# SI5324_CDR_WR_oscillators.net
KiCad netlist of a schematic drawn in Altium Designer
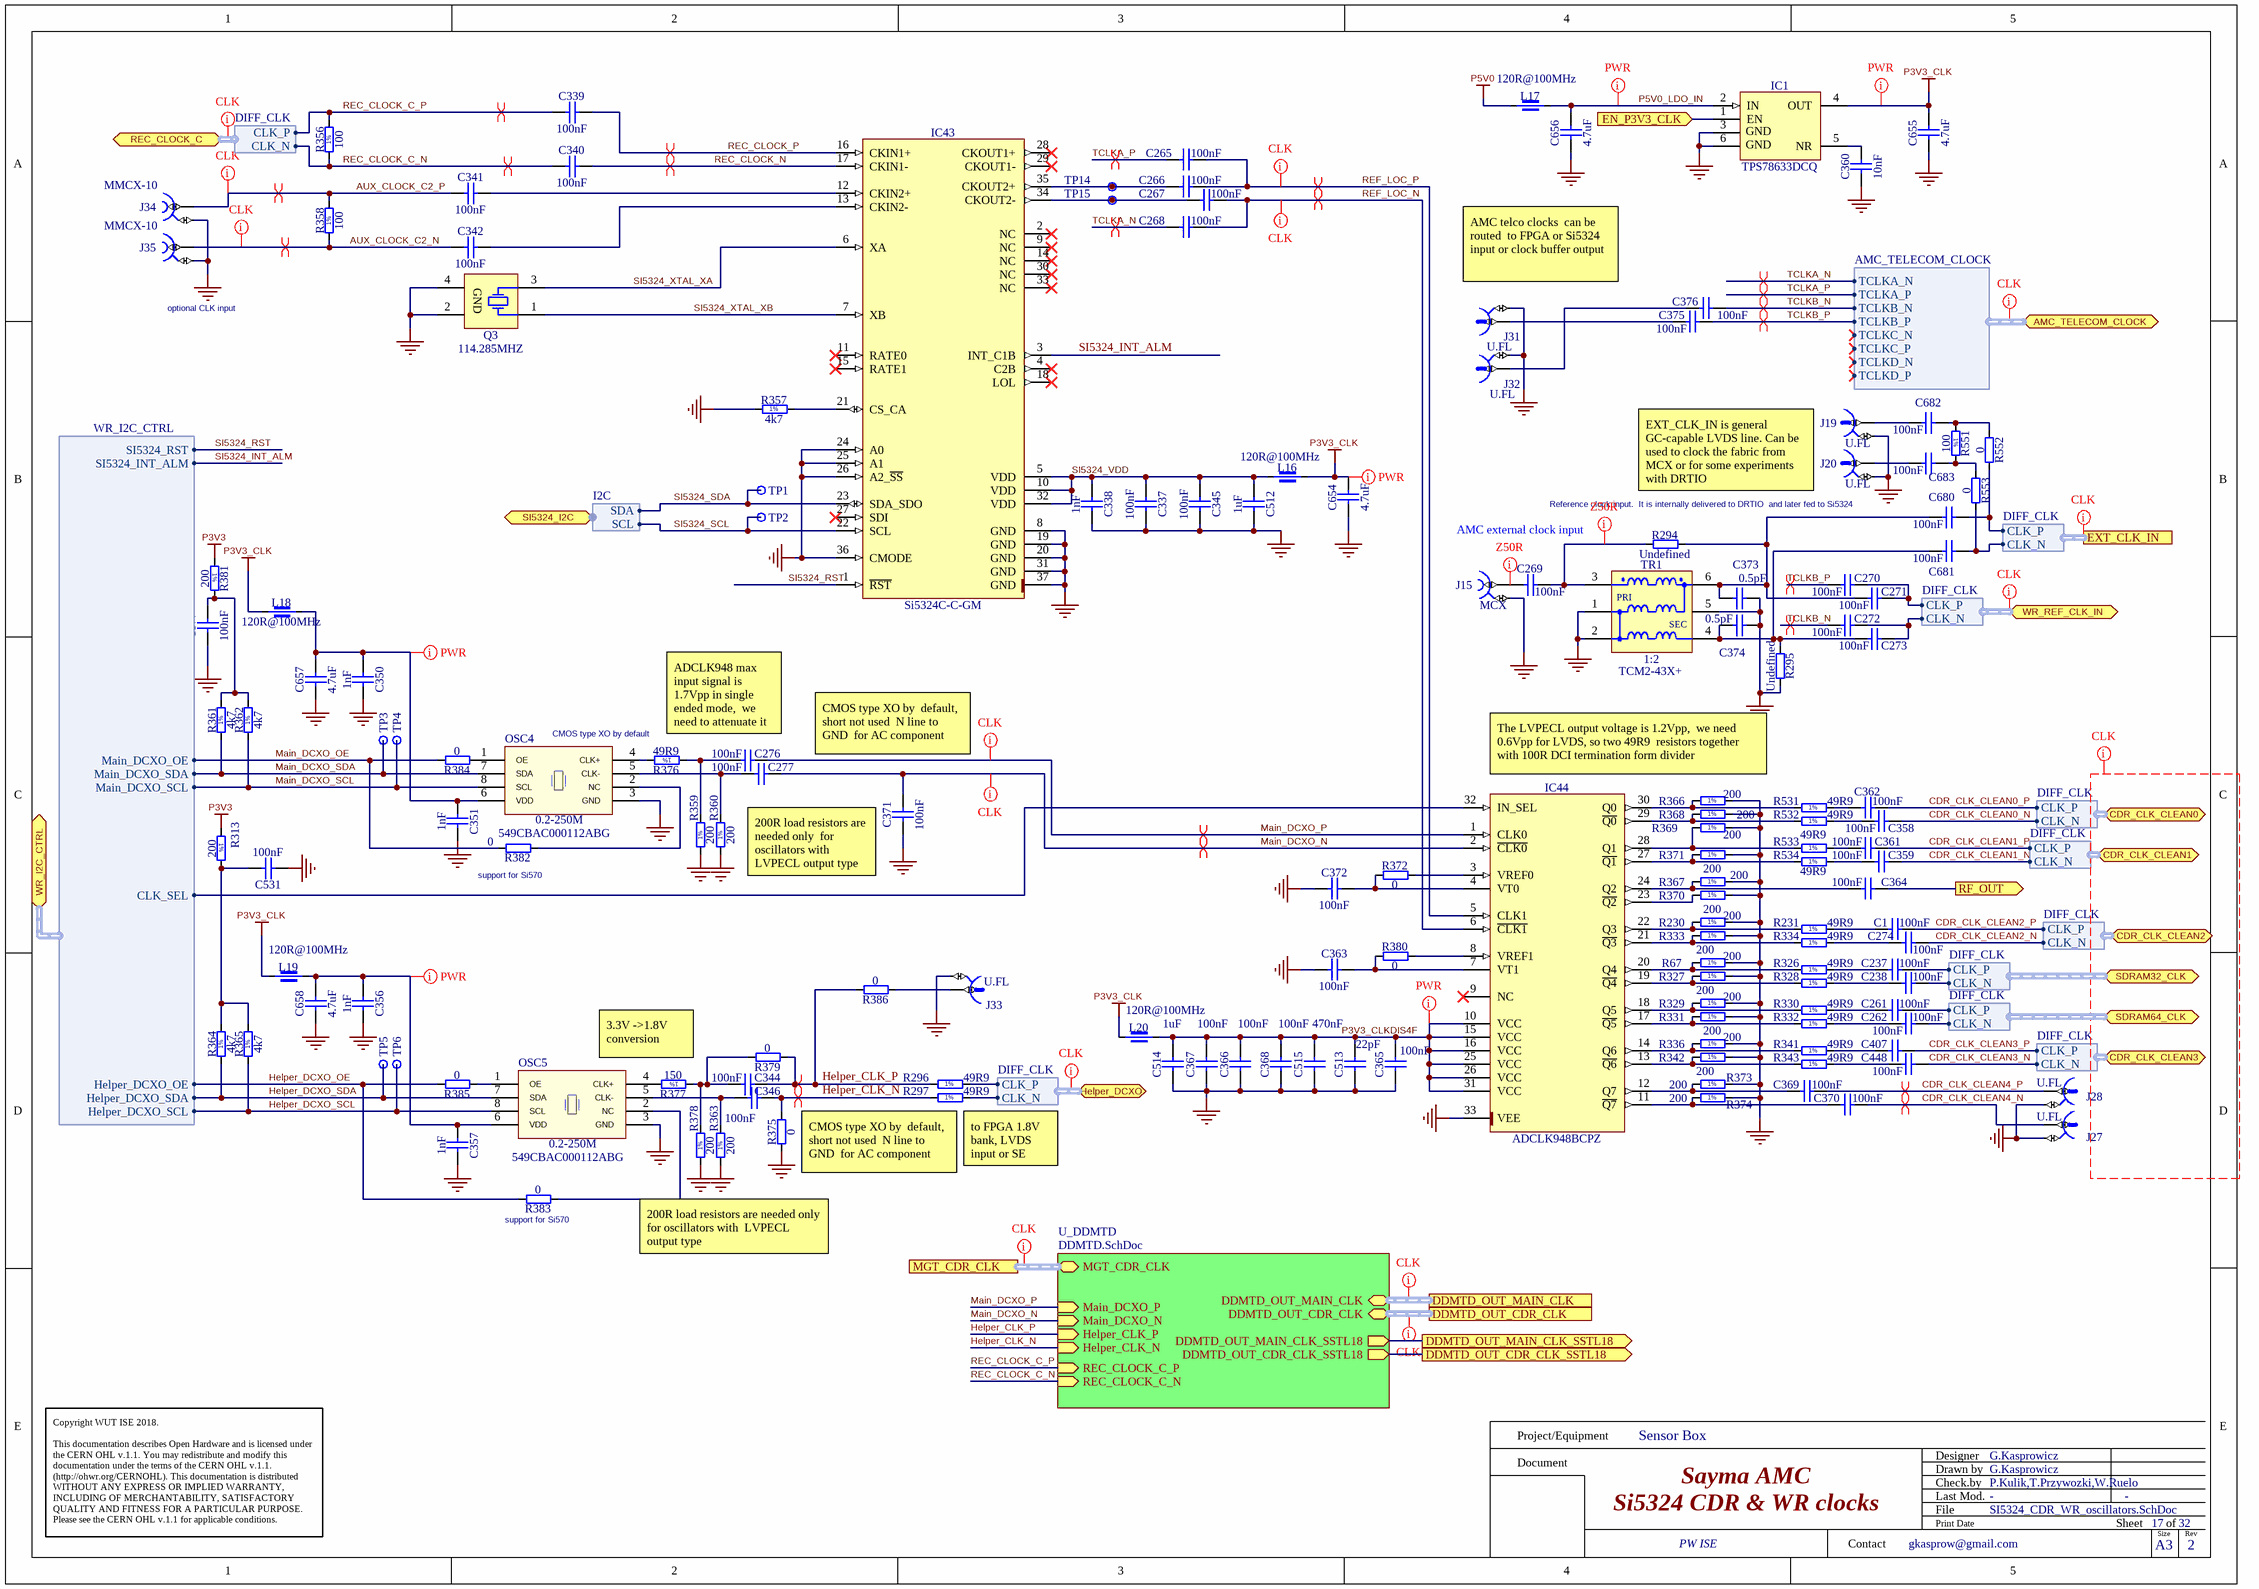
[diagram p0: SI5324_CDR_WR_oscillators.SchDoc]

(export (version "E")
  (design (tool "Eeschema 10.0.6"))
  (components
    (comp (ref "C1")
      (value "100nF")
      (footprint "CAPC0603X33N")
      (description "Non-polarised capacitor")
      (fields
        (field (name "MANUFACTURER PART NUMBER") "CC0201_100NF_6.3V_10%_X5R")
        (field (name "MANUFACTURER") "GENERIC")
        (field (name "AUTHOR") "CERN DEM JLC")
      )
      (libsource (lib "Capacitors") (part "Capacitor - non polarized"))
    )
    (comp (ref "C237")
      (value "100nF")
      (footprint "CAPC0603X33N")
      (description "Non-polarised capacitor")
      (fields
        (field (name "MANUFACTURER PART NUMBER") "CC0201_100NF_6.3V_10%_X5R")
        (field (name "MANUFACTURER") "GENERIC")
        (field (name "AUTHOR") "CERN DEM JLC")
      )
      (libsource (lib "Capacitors") (part "Capacitor - non polarized"))
    )
    (comp (ref "C238")
      (value "100nF")
      (footprint "CAPC0603X33N")
      (description "Non-polarised capacitor")
      (fields
        (field (name "MANUFACTURER PART NUMBER") "CC0201_100NF_6.3V_10%_X5R")
        (field (name "MANUFACTURER") "GENERIC")
        (field (name "AUTHOR") "CERN DEM JLC")
      )
      (libsource (lib "Capacitors") (part "Capacitor - non polarized"))
    )
    (comp (ref "C261")
      (value "100nF")
      (footprint "CAPC0603X33N")
      (description "Non-polarised capacitor")
      (fields
        (field (name "MANUFACTURER PART NUMBER") "CC0201_100NF_6.3V_10%_X5R")
        (field (name "MANUFACTURER") "GENERIC")
        (field (name "AUTHOR") "CERN DEM JLC")
      )
      (libsource (lib "Capacitors") (part "Capacitor - non polarized"))
    )
    (comp (ref "C262")
      (value "100nF")
      (footprint "CAPC0603X33N")
      (description "Non-polarised capacitor")
      (fields
        (field (name "MANUFACTURER PART NUMBER") "CC0201_100NF_6.3V_10%_X5R")
        (field (name "MANUFACTURER") "GENERIC")
        (field (name "AUTHOR") "CERN DEM JLC")
      )
      (libsource (lib "Capacitors") (part "Capacitor - non polarized"))
    )
    (comp (ref "C265")
      (value "100nF")
      (footprint "CAPC1005X55N")
      (description "Non-polarised capacitor")
      (fields
        (field (name "MANUFACTURER PART NUMBER") "CC0402_100NF_16V_10%_X5R")
        (field (name "MANUFACTURER") "GENERIC")
        (field (name "AUTHOR") "CERN DEM JLC")
      )
      (libsource (lib "Capacitors") (part "Capacitor - non polarized"))
    )
    (comp (ref "C266")
      (value "100nF")
      (footprint "CAPC1005X55N")
      (description "Non-polarised capacitor")
      (fields
        (field (name "MANUFACTURER PART NUMBER") "CC0402_100NF_16V_10%_X5R")
        (field (name "MANUFACTURER") "GENERIC")
        (field (name "AUTHOR") "CERN DEM JLC")
      )
      (libsource (lib "Capacitors") (part "Capacitor - non polarized"))
    )
    (comp (ref "C267")
      (value "100nF")
      (footprint "CAPC1005X55N")
      (description "Non-polarised capacitor")
      (fields
        (field (name "MANUFACTURER PART NUMBER") "CC0402_100NF_16V_10%_X5R")
        (field (name "MANUFACTURER") "GENERIC")
        (field (name "AUTHOR") "CERN DEM JLC")
      )
      (libsource (lib "Capacitors") (part "Capacitor - non polarized"))
    )
    (comp (ref "C268")
      (value "100nF")
      (footprint "CAPC1005X55N")
      (description "Non-polarised capacitor")
      (fields
        (field (name "MANUFACTURER PART NUMBER") "CC0402_100NF_16V_10%_X5R")
        (field (name "MANUFACTURER") "GENERIC")
        (field (name "AUTHOR") "CERN DEM JLC")
      )
      (libsource (lib "Capacitors") (part "Capacitor - non polarized"))
    )
    (comp (ref "C269")
      (value "100nF")
      (footprint "CAPC1005X55N")
      (description "Non-polarised capacitor")
      (fields
        (field (name "MANUFACTURER PART NUMBER") "CC0402_100NF_16V_10%_X5R")
        (field (name "MANUFACTURER") "GENERIC")
        (field (name "AUTHOR") "CERN DEM JLC")
      )
      (libsource (lib "Capacitors") (part "Capacitor - non polarized"))
    )
    (comp (ref "C270")
      (value "100nF")
      (footprint "CAPC1005X55N")
      (description "Non-polarised capacitor")
      (fields
        (field (name "MANUFACTURER PART NUMBER") "CC0402_100NF_16V_10%_X5R")
        (field (name "MANUFACTURER") "GENERIC")
        (field (name "AUTHOR") "CERN DEM JLC")
      )
      (libsource (lib "Capacitors") (part "Capacitor - non polarized"))
    )
    (comp (ref "C271")
      (value "100nF")
      (footprint "CAPC1005X55N")
      (description "Non-polarised capacitor")
      (fields
        (field (name "MANUFACTURER PART NUMBER") "CC0402_100NF_16V_10%_X5R")
        (field (name "MANUFACTURER") "GENERIC")
        (field (name "AUTHOR") "CERN DEM JLC")
      )
      (libsource (lib "Capacitors") (part "Capacitor - non polarized"))
    )
    (comp (ref "C272")
      (value "100nF")
      (footprint "CAPC1005X55N")
      (description "Non-polarised capacitor")
      (fields
        (field (name "MANUFACTURER PART NUMBER") "CC0402_100NF_16V_10%_X5R")
        (field (name "MANUFACTURER") "GENERIC")
        (field (name "AUTHOR") "CERN DEM JLC")
      )
      (libsource (lib "Capacitors") (part "Capacitor - non polarized"))
    )
    (comp (ref "C273")
      (value "100nF")
      (footprint "CAPC1005X55N")
      (description "Non-polarised capacitor")
      (fields
        (field (name "MANUFACTURER PART NUMBER") "CC0402_100NF_16V_10%_X5R")
        (field (name "MANUFACTURER") "GENERIC")
        (field (name "AUTHOR") "CERN DEM JLC")
      )
      (libsource (lib "Capacitors") (part "Capacitor - non polarized"))
    )
    (comp (ref "C274")
      (value "100nF")
      (footprint "CAPC0603X33N")
      (description "Non-polarised capacitor")
      (fields
        (field (name "MANUFACTURER PART NUMBER") "CC0201_100NF_6.3V_10%_X5R")
        (field (name "MANUFACTURER") "GENERIC")
        (field (name "AUTHOR") "CERN DEM JLC")
      )
      (libsource (lib "Capacitors") (part "Capacitor - non polarized"))
    )
    (comp (ref "C276")
      (value "100nF")
      (footprint "CAPC1005X55N")
      (description "Non-polarised capacitor")
      (fields
        (field (name "MANUFACTURER PART NUMBER") "CC0402_100NF_16V_10%_X5R")
        (field (name "MANUFACTURER") "GENERIC")
        (field (name "AUTHOR") "CERN DEM JLC")
      )
      (libsource (lib "Capacitors") (part "Capacitor - non polarized"))
    )
    (comp (ref "C277")
      (value "100nF")
      (footprint "CAPC1005X55N")
      (description "Non-polarised capacitor")
      (fields
        (field (name "MANUFACTURER PART NUMBER") "CC0402_100NF_16V_10%_X5R")
        (field (name "MANUFACTURER") "GENERIC")
        (field (name "AUTHOR") "CERN DEM JLC")
      )
      (libsource (lib "Capacitors") (part "Capacitor - non polarized"))
    )
    (comp (ref "C337")
      (value "100nF")
      (footprint "CAPC0603X33N")
      (description "Non-polarised capacitor")
      (fields
        (field (name "MANUFACTURER PART NUMBER") "CC0201_100NF_6.3V_10%_X5R")
        (field (name "MANUFACTURER") "GENERIC")
        (field (name "AUTHOR") "CERN DEM JLC")
      )
      (libsource (lib "Capacitors") (part "Capacitor - non polarized"))
    )
    (comp (ref "C338")
      (value "1nF")
      (footprint "CAPC0603X33N")
      (description "Non-polarised capacitor")
      (fields
        (field (name "MANUFACTURER PART NUMBER") "CC0201_1NF_16V_10%_X5R")
        (field (name "MANUFACTURER") "GENERIC")
        (field (name "AUTHOR") "CERN DEM JLC")
      )
      (libsource (lib "Capacitors") (part "Capacitor - non polarized"))
    )
    (comp (ref "C339")
      (value "100nF")
      (footprint "CAPC0603X33N")
      (description "Non-polarised capacitor")
      (fields
        (field (name "MANUFACTURER PART NUMBER") "CC0201_100NF_6.3V_10%_X5R")
        (field (name "MANUFACTURER") "GENERIC")
        (field (name "AUTHOR") "CERN DEM JLC")
      )
      (libsource (lib "Capacitors") (part "Capacitor - non polarized"))
    )
    (comp (ref "C340")
      (value "100nF")
      (footprint "CAPC0603X33N")
      (description "Non-polarised capacitor")
      (fields
        (field (name "MANUFACTURER PART NUMBER") "CC0201_100NF_6.3V_10%_X5R")
        (field (name "MANUFACTURER") "GENERIC")
        (field (name "AUTHOR") "CERN DEM JLC")
      )
      (libsource (lib "Capacitors") (part "Capacitor - non polarized"))
    )
    (comp (ref "C341")
      (value "100nF")
      (footprint "CAPC0603X33N")
      (description "Non-polarised capacitor")
      (fields
        (field (name "MANUFACTURER PART NUMBER") "CC0201_100NF_6.3V_10%_X5R")
        (field (name "MANUFACTURER") "GENERIC")
        (field (name "AUTHOR") "CERN DEM JLC")
      )
      (libsource (lib "Capacitors") (part "Capacitor - non polarized"))
    )
    (comp (ref "C342")
      (value "100nF")
      (footprint "CAPC0603X33N")
      (description "Non-polarised capacitor")
      (fields
        (field (name "MANUFACTURER PART NUMBER") "CC0201_100NF_6.3V_10%_X5R")
        (field (name "MANUFACTURER") "GENERIC")
        (field (name "AUTHOR") "CERN DEM JLC")
      )
      (libsource (lib "Capacitors") (part "Capacitor - non polarized"))
    )
    (comp (ref "C344")
      (value "100nF")
      (footprint "CAPC1005X55N")
      (description "Non-polarised capacitor")
      (fields
        (field (name "MANUFACTURER PART NUMBER") "CC0402_100NF_16V_10%_X5R")
        (field (name "MANUFACTURER") "GENERIC")
        (field (name "AUTHOR") "CERN DEM JLC")
      )
      (libsource (lib "Capacitors") (part "Capacitor - non polarized"))
    )
    (comp (ref "C345")
      (value "100nF")
      (footprint "CAPC0603X33N")
      (description "Non-polarised capacitor")
      (fields
        (field (name "MANUFACTURER PART NUMBER") "CC0201_100NF_6.3V_10%_X5R")
        (field (name "MANUFACTURER") "GENERIC")
        (field (name "AUTHOR") "CERN DEM JLC")
      )
      (libsource (lib "Capacitors") (part "Capacitor - non polarized"))
    )
    (comp (ref "C346")
      (value "100nF")
      (footprint "CAPC1005X55N")
      (description "Non-polarised capacitor")
      (fields
        (field (name "MANUFACTURER PART NUMBER") "CC0402_100NF_16V_10%_X5R")
        (field (name "MANUFACTURER") "GENERIC")
        (field (name "AUTHOR") "CERN DEM JLC")
      )
      (libsource (lib "Capacitors") (part "Capacitor - non polarized"))
    )
    (comp (ref "C350")
      (value "1nF")
      (footprint "CAPC0603X33N")
      (description "Non-polarised capacitor")
      (fields
        (field (name "MANUFACTURER PART NUMBER") "CC0201_1NF_16V_10%_X5R")
        (field (name "MANUFACTURER") "GENERIC")
        (field (name "AUTHOR") "CERN DEM JLC")
      )
      (libsource (lib "Capacitors") (part "Capacitor - non polarized"))
    )
    (comp (ref "C351")
      (value "1nF")
      (footprint "CAPC0603X33N")
      (description "Non-polarised capacitor")
      (fields
        (field (name "MANUFACTURER PART NUMBER") "CC0201_1NF_16V_10%_X5R")
        (field (name "MANUFACTURER") "GENERIC")
        (field (name "AUTHOR") "CERN DEM JLC")
      )
      (libsource (lib "Capacitors") (part "Capacitor - non polarized"))
    )
    (comp (ref "C356")
      (value "1nF")
      (footprint "CAPC0603X33N")
      (description "Non-polarised capacitor")
      (fields
        (field (name "MANUFACTURER PART NUMBER") "CC0201_1NF_16V_10%_X5R")
        (field (name "MANUFACTURER") "GENERIC")
        (field (name "AUTHOR") "CERN DEM JLC")
      )
      (libsource (lib "Capacitors") (part "Capacitor - non polarized"))
    )
    (comp (ref "C357")
      (value "1nF")
      (footprint "CAPC0603X33N")
      (description "Non-polarised capacitor")
      (fields
        (field (name "MANUFACTURER PART NUMBER") "CC0201_1NF_16V_10%_X5R")
        (field (name "MANUFACTURER") "GENERIC")
        (field (name "AUTHOR") "CERN DEM JLC")
      )
      (libsource (lib "Capacitors") (part "Capacitor - non polarized"))
    )
    (comp (ref "C358")
      (value "100nF")
      (footprint "CAPC0603X33N")
      (description "Non-polarised capacitor")
      (fields
        (field (name "MANUFACTURER PART NUMBER") "CC0201_100NF_6.3V_10%_X5R")
        (field (name "MANUFACTURER") "GENERIC")
        (field (name "AUTHOR") "CERN DEM JLC")
      )
      (libsource (lib "Capacitors") (part "Capacitor - non polarized"))
    )
    (comp (ref "C359")
      (value "100nF")
      (footprint "CAPC0603X33N")
      (description "Non-polarised capacitor")
      (fields
        (field (name "MANUFACTURER PART NUMBER") "CC0201_100NF_6.3V_10%_X5R")
        (field (name "MANUFACTURER") "GENERIC")
        (field (name "AUTHOR") "CERN DEM JLC")
      )
      (libsource (lib "Capacitors") (part "Capacitor - non polarized"))
    )
    (comp (ref "C360")
      (value "10nF")
      (footprint "CAPC1608X87N")
      (description "Non-polarised capacitor")
      (fields
        (field (name "PART NUMBER") "CC0603_10NF_50V_5%_C0G")
        (field (name "VOLTAGE") "50V")
        (field (name "AUTHOR") "CERN DEM JLC")
      )
      (libsource (lib "Capacitors") (part "Capacitor - non polarized"))
    )
    (comp (ref "C361")
      (value "100nF")
      (footprint "CAPC0603X33N")
      (description "Non-polarised capacitor")
      (fields
        (field (name "MANUFACTURER PART NUMBER") "CC0201_100NF_6.3V_10%_X5R")
        (field (name "MANUFACTURER") "GENERIC")
        (field (name "AUTHOR") "CERN DEM JLC")
      )
      (libsource (lib "Capacitors") (part "Capacitor - non polarized"))
    )
    (comp (ref "C362")
      (value "100nF")
      (footprint "CAPC0603X33N")
      (description "Non-polarised capacitor")
      (fields
        (field (name "MANUFACTURER PART NUMBER") "CC0201_100NF_6.3V_10%_X5R")
        (field (name "MANUFACTURER") "GENERIC")
        (field (name "AUTHOR") "CERN DEM JLC")
      )
      (libsource (lib "Capacitors") (part "Capacitor - non polarized"))
    )
    (comp (ref "C363")
      (value "100nF")
      (footprint "CAPC0603X33N")
      (description "Non-polarised capacitor")
      (fields
        (field (name "MANUFACTURER PART NUMBER") "CC0201_100NF_6.3V_10%_X5R")
        (field (name "MANUFACTURER") "GENERIC")
        (field (name "AUTHOR") "CERN DEM JLC")
      )
      (libsource (lib "Capacitors") (part "Capacitor - non polarized"))
    )
    (comp (ref "C364")
      (value "100nF")
      (footprint "CAPC0603X33N")
      (description "Non-polarised capacitor")
      (fields
        (field (name "MANUFACTURER PART NUMBER") "CC0201_100NF_6.3V_10%_X5R")
        (field (name "MANUFACTURER") "GENERIC")
        (field (name "AUTHOR") "CERN DEM JLC")
      )
      (libsource (lib "Capacitors") (part "Capacitor - non polarized"))
    )
    (comp (ref "C365")
      (value "100nF")
      (footprint "CAPC0603X33N")
      (description "Non-polarised capacitor")
      (fields
        (field (name "MANUFACTURER PART NUMBER") "CC0201_100NF_6.3V_10%_X5R")
        (field (name "MANUFACTURER") "GENERIC")
        (field (name "AUTHOR") "CERN DEM JLC")
      )
      (libsource (lib "Capacitors") (part "Capacitor - non polarized"))
    )
    (comp (ref "C366")
      (value "100nF")
      (footprint "CAPC0603X33N")
      (description "Non-polarised capacitor")
      (fields
        (field (name "MANUFACTURER PART NUMBER") "CC0201_100NF_6.3V_10%_X5R")
        (field (name "MANUFACTURER") "GENERIC")
        (field (name "AUTHOR") "CERN DEM JLC")
      )
      (libsource (lib "Capacitors") (part "Capacitor - non polarized"))
    )
    (comp (ref "C367")
      (value "100nF")
      (footprint "CAPC0603X33N")
      (description "Non-polarised capacitor")
      (fields
        (field (name "MANUFACTURER PART NUMBER") "CC0201_100NF_6.3V_10%_X5R")
        (field (name "MANUFACTURER") "GENERIC")
        (field (name "AUTHOR") "CERN DEM JLC")
      )
      (libsource (lib "Capacitors") (part "Capacitor - non polarized"))
    )
    (comp (ref "C368")
      (value "100nF")
      (footprint "CAPC0603X33N")
      (description "Non-polarised capacitor")
      (fields
        (field (name "MANUFACTURER PART NUMBER") "CC0201_100NF_6.3V_10%_X5R")
        (field (name "MANUFACTURER") "GENERIC")
        (field (name "AUTHOR") "CERN DEM JLC")
      )
      (libsource (lib "Capacitors") (part "Capacitor - non polarized"))
    )
    (comp (ref "C369")
      (value "100nF")
      (footprint "CAPC0603X33N")
      (description "Non-polarised capacitor")
      (fields
        (field (name "MANUFACTURER PART NUMBER") "CC0201_100NF_6.3V_10%_X5R")
        (field (name "MANUFACTURER") "GENERIC")
        (field (name "AUTHOR") "CERN DEM JLC")
      )
      (libsource (lib "Capacitors") (part "Capacitor - non polarized"))
    )
    (comp (ref "C370")
      (value "100nF")
      (footprint "CAPC0603X33N")
      (description "Non-polarised capacitor")
      (fields
        (field (name "MANUFACTURER PART NUMBER") "CC0201_100NF_6.3V_10%_X5R")
        (field (name "MANUFACTURER") "GENERIC")
        (field (name "AUTHOR") "CERN DEM JLC")
      )
      (libsource (lib "Capacitors") (part "Capacitor - non polarized"))
    )
    (comp (ref "C371")
      (value "100nF")
      (footprint "CAPC0603X33N")
      (description "Non-polarised capacitor")
      (fields
        (field (name "MANUFACTURER PART NUMBER") "CC0201_100NF_6.3V_10%_X5R")
        (field (name "MANUFACTURER") "GENERIC")
        (field (name "AUTHOR") "CERN DEM JLC")
      )
      (libsource (lib "Capacitors") (part "Capacitor - non polarized"))
    )
    (comp (ref "C372")
      (value "100nF")
      (footprint "CAPC0603X33N")
      (description "Non-polarised capacitor")
      (fields
        (field (name "MANUFACTURER PART NUMBER") "CC0201_100NF_6.3V_10%_X5R")
        (field (name "MANUFACTURER") "GENERIC")
        (field (name "AUTHOR") "CERN DEM JLC")
      )
      (libsource (lib "Capacitors") (part "Capacitor - non polarized"))
    )
    (comp (ref "C373")
      (value "0.5pF")
      (footprint "CAPC1005X50N")
      (description "Non-polarised capacitor")
      (fields
        (field (name "PART NUMBER") "CC0402_0.5PF_25V_0.05PF_AVX_04023J0R5ABSTR")
        (field (name "VOLTAGE") "25V")
        (field (name "AUTHOR") "CERN DEM JLC")
      )
      (libsource (lib "Capacitors") (part "Capacitor - non polarized"))
    )
    (comp (ref "C374")
      (value "0.5pF")
      (footprint "CAPC1005X50N")
      (description "Non-polarised capacitor")
      (fields
        (field (name "PART NUMBER") "CC0402_0.5PF_25V_0.05PF_AVX_04023J0R5ABSTR")
        (field (name "VOLTAGE") "25V")
        (field (name "AUTHOR") "CERN DEM JLC")
      )
      (libsource (lib "Capacitors") (part "Capacitor - non polarized"))
    )
    (comp (ref "C375")
      (value "100nF")
      (footprint "CAPC0603X33N")
      (description "Non-polarised capacitor")
      (fields
        (field (name "MANUFACTURER PART NUMBER") "CC0201_100NF_6.3V_10%_X5R")
        (field (name "MANUFACTURER") "GENERIC")
        (field (name "AUTHOR") "CERN DEM JLC")
      )
      (libsource (lib "Capacitors") (part "Capacitor - non polarized"))
    )
    (comp (ref "C376")
      (value "100nF")
      (footprint "CAPC0603X33N")
      (description "Non-polarised capacitor")
      (fields
        (field (name "MANUFACTURER PART NUMBER") "CC0201_100NF_6.3V_10%_X5R")
        (field (name "MANUFACTURER") "GENERIC")
        (field (name "AUTHOR") "CERN DEM JLC")
      )
      (libsource (lib "Capacitors") (part "Capacitor - non polarized"))
    )
    (comp (ref "C377")
      (value "100nF")
      (footprint "CAPC0603X33N")
      (description "Non-polarised capacitor")
      (fields
        (field (name "MANUFACTURER PART NUMBER") "CC0201_100NF_6.3V_10%_X5R")
        (field (name "MANUFACTURER") "GENERIC")
        (field (name "AUTHOR") "CERN DEM JLC")
      )
      (libsource (lib "Capacitors") (part "Capacitor - non polarized"))
    )
    (comp (ref "C407")
      (value "100nF")
      (footprint "CAPC0603X33N")
      (description "Non-polarised capacitor")
      (fields
        (field (name "MANUFACTURER PART NUMBER") "CC0201_100NF_6.3V_10%_X5R")
        (field (name "MANUFACTURER") "GENERIC")
        (field (name "AUTHOR") "CERN DEM JLC")
      )
      (libsource (lib "Capacitors") (part "Capacitor - non polarized"))
    )
    (comp (ref "C448")
      (value "100nF")
      (footprint "CAPC0603X33N")
      (description "Non-polarised capacitor")
      (fields
        (field (name "MANUFACTURER PART NUMBER") "CC0201_100NF_6.3V_10%_X5R")
        (field (name "MANUFACTURER") "GENERIC")
        (field (name "AUTHOR") "CERN DEM JLC")
      )
      (libsource (lib "Capacitors") (part "Capacitor - non polarized"))
    )
    (comp (ref "C512")
      (value "1uF")
      (footprint "CAPC1005X55N")
      (description "Non-polarised capacitor")
      (fields
        (field (name "MANUFACTURER PART NUMBER") "CC0402_1UF_16V_10%_X5R")
        (field (name "MANUFACTURER") "GENERIC")
        (field (name "AUTHOR") "CERN DEM JLC")
      )
      (libsource (lib "Capacitors") (part "Capacitor - non polarized"))
    )
    (comp (ref "C513")
      (value "22pF")
      (footprint "CAPC1005X55N")
      (description "Non-polarised capacitor")
      (fields
        (field (name "MANUFACTURER PART NUMBER") "CC0402_22PF_50V_5%_C0G")
        (field (name "MANUFACTURER") "GENERIC")
        (field (name "AUTHOR") "CERN DEM JLC")
      )
      (libsource (lib "Capacitors") (part "Capacitor - non polarized"))
    )
    (comp (ref "C514")
      (value "1uF")
      (footprint "CAPC1005X55N")
      (description "Non-polarised capacitor")
      (fields
        (field (name "MANUFACTURER PART NUMBER") "CC0402_1UF_16V_10%_X5R")
        (field (name "MANUFACTURER") "GENERIC")
        (field (name "AUTHOR") "CERN DEM JLC")
      )
      (libsource (lib "Capacitors") (part "Capacitor - non polarized"))
    )
    (comp (ref "C515")
      (value "470nF")
      (footprint "CAPC1005X55N")
      (description "Non-polarised capacitor")
      (fields
        (field (name "MANUFACTURER PART NUMBER") "CC0402_470NF_16V_10%_X5R")
        (field (name "MANUFACTURER") "GENERIC")
        (field (name "AUTHOR") "CERN DEM JLC")
      )
      (libsource (lib "Capacitors") (part "Capacitor - non polarized"))
    )
    (comp (ref "C531")
      (value "100nF")
      (footprint "CAPC0603X33N")
      (description "Non-polarised capacitor")
      (fields
        (field (name "MANUFACTURER PART NUMBER") "CC0201_100NF_6.3V_10%_X5R")
        (field (name "MANUFACTURER") "GENERIC")
        (field (name "AUTHOR") "CERN DEM JLC")
      )
      (libsource (lib "Capacitors") (part "Capacitor - non polarized"))
    )
    (comp (ref "C654")
      (value "4.7uF")
      (footprint "CAPC1608X90N")
      (description "Non-polarised capacitor")
      (fields
        (field (name "MANUFACTURER PART NUMBER") "CC0603_4.7UF_25V_10%_X5R")
        (field (name "MANUFACTURER") "GENERIC")
        (field (name "AUTHOR") "CERN DEM JLC")
      )
      (libsource (lib "Capacitors") (part "Capacitor - non polarized"))
    )
    (comp (ref "C655")
      (value "4.7uF")
      (footprint "CAPC1608X90N")
      (description "Non-polarised capacitor")
      (fields
        (field (name "MANUFACTURER PART NUMBER") "CC0603_4.7UF_25V_10%_X5R")
        (field (name "MANUFACTURER") "GENERIC")
        (field (name "AUTHOR") "CERN DEM JLC")
      )
      (libsource (lib "Capacitors") (part "Capacitor - non polarized"))
    )
    (comp (ref "C656")
      (value "4.7uF")
      (footprint "CAPC1608X90N")
      (description "Non-polarised capacitor")
      (fields
        (field (name "MANUFACTURER PART NUMBER") "CC0603_4.7UF_25V_10%_X5R")
        (field (name "MANUFACTURER") "GENERIC")
        (field (name "AUTHOR") "CERN DEM JLC")
      )
      (libsource (lib "Capacitors") (part "Capacitor - non polarized"))
    )
    (comp (ref "C657")
      (value "4.7uF")
      (footprint "CAPC1608X90N")
      (description "Non-polarised capacitor")
      (fields
        (field (name "MANUFACTURER PART NUMBER") "CC0603_4.7UF_25V_10%_X5R")
        (field (name "MANUFACTURER") "GENERIC")
        (field (name "AUTHOR") "CERN DEM JLC")
      )
      (libsource (lib "Capacitors") (part "Capacitor - non polarized"))
    )
    (comp (ref "C658")
      (value "4.7uF")
      (footprint "CAPC1608X90N")
      (description "Non-polarised capacitor")
      (fields
        (field (name "MANUFACTURER PART NUMBER") "CC0603_4.7UF_25V_10%_X5R")
        (field (name "MANUFACTURER") "GENERIC")
        (field (name "AUTHOR") "CERN DEM JLC")
      )
      (libsource (lib "Capacitors") (part "Capacitor - non polarized"))
    )
    (comp (ref "C680")
      (value "100nF")
      (footprint "CAPC1005X55N")
      (description "Non-polarised capacitor")
      (fields
        (field (name "MANUFACTURER PART NUMBER") "CC0402_100NF_16V_10%_X5R")
        (field (name "MANUFACTURER") "GENERIC")
        (field (name "AUTHOR") "CERN DEM JLC")
      )
      (libsource (lib "Capacitors") (part "Capacitor - non polarized"))
    )
    (comp (ref "C681")
      (value "100nF")
      (footprint "CAPC1005X55N")
      (description "Non-polarised capacitor")
      (fields
        (field (name "MANUFACTURER PART NUMBER") "CC0402_100NF_16V_10%_X5R")
        (field (name "MANUFACTURER") "GENERIC")
        (field (name "AUTHOR") "CERN DEM JLC")
      )
      (libsource (lib "Capacitors") (part "Capacitor - non polarized"))
    )
    (comp (ref "C682")
      (value "100nF")
      (footprint "CAPC1005X55N")
      (description "Non-polarised capacitor")
      (fields
        (field (name "MANUFACTURER PART NUMBER") "CC0402_100NF_16V_10%_X5R")
        (field (name "MANUFACTURER") "GENERIC")
        (field (name "AUTHOR") "CERN DEM JLC")
      )
      (libsource (lib "Capacitors") (part "Capacitor - non polarized"))
    )
    (comp (ref "C683")
      (value "100nF")
      (footprint "CAPC1005X55N")
      (description "Non-polarised capacitor")
      (fields
        (field (name "MANUFACTURER PART NUMBER") "CC0402_100NF_16V_10%_X5R")
        (field (name "MANUFACTURER") "GENERIC")
        (field (name "AUTHOR") "CERN DEM JLC")
      )
      (libsource (lib "Capacitors") (part "Capacitor - non polarized"))
    )
    (comp (ref "IC1")
      (value "TPS78633DCQ")
      (footprint "SOT127P700X180-6N")
      (description "Ultralow-Noise, High-PSRR, Fast, RF, 1.5A Low-Dropout Linear Regulator")
      (fields (field (name "MANUFACTURER") "TEXAS INSTRUMENTS") (field (name "AUTHOR") "CERN DEM JMW"))
      (libsource (lib "ICs And Semiconductors") (part "TPS786xxDCQ"))
    )
    (comp (ref "IC43")
      (value "Si5324C-C-GM")
      (footprint "QFN50P600X600X90-37N-S425")
      (description "Any Frequency Precision Clock Multiplier/Jitter Attenuator")
      (fields (field (name "MANUFACTURER") "SILICON LABS") (field (name "AUTHOR") "CERN DEM JLC"))
      (libsource (lib "ICs And Semiconductors") (part "Si5324"))
    )
    (comp (ref "IC44")
      (value "ADCLK948BCPZ")
      (footprint "QFN50P500X500X80-33N-S285")
      (description "Two Selectable Inputs, 8 LVPECL Outputs, SiGe Clock Fanout Buffer")
      (fields (field (name "MANUFACTURER") "ANALOG DEVICES") (field (name "AUTHOR") "CERN DEM MR"))
      (libsource (lib "ICs And Semiconductors") (part "ADCLK948"))
    )
    (comp (ref "J15")
      (value "MCX")
      (footprint "AMPHENOL_ARF2521-ND")
      (fields
        (field (name "PART NUMBER") "AMPHENOL_ARF2521-ND")
        (field (name "MANUFACTURER") "AMPHENOL")
        (field (name "AUTHOR") "GK")
      )
      (libsource (lib "LIBRARY_SCH") (part "CON_MCX"))
    )
    (comp (ref "J19")
      (value "U.FL")
      (footprint "HIROSE_U.FL-R-SMT-1(10)")
      (fields
        (field (name "PART NUMBER") "HIROSE_U.FL-R-SMT-1(10)")
        (field (name "MANUFACTURER") "HIROSE (HRS)")
        (field (name "MANUFACTURER PART NUMBER") "U.FL-R-SMT-1(10)")
        (field (name "AUTHOR") "CERN DEM JLC")
      )
      (libsource (lib "Connectors") (part "Coax_1Male_1Shield"))
    )
    (comp (ref "J20")
      (value "U.FL")
      (footprint "HIROSE_U.FL-R-SMT-1(10)")
      (fields
        (field (name "PART NUMBER") "HIROSE_U.FL-R-SMT-1(10)")
        (field (name "MANUFACTURER") "HIROSE (HRS)")
        (field (name "MANUFACTURER PART NUMBER") "U.FL-R-SMT-1(10)")
        (field (name "AUTHOR") "CERN DEM JLC")
      )
      (libsource (lib "Connectors") (part "Coax_1Male_1Shield"))
    )
    (comp (ref "J27")
      (value "U.FL")
      (footprint "HIROSE_U.FL-R-SMT-1(10)")
      (fields
        (field (name "MANUFACTURER PART NUMBER") "U.FL-R-SMT-1(10)")
        (field (name "MANUFACTURER") "HIROSE (HRS)")
        (field (name "PART NUMBER") "HIROSE_U.FL-R-SMT-1(10)")
        (field (name "AUTHOR") "CERN DEM JLC")
      )
      (libsource (lib "") (part "Coax_1Male_1Shield_1"))
    )
    (comp (ref "J28")
      (value "U.FL")
      (footprint "HIROSE_U.FL-R-SMT-1(10)")
      (fields
        (field (name "MANUFACTURER PART NUMBER") "U.FL-R-SMT-1(10)")
        (field (name "MANUFACTURER") "HIROSE (HRS)")
        (field (name "PART NUMBER") "HIROSE_U.FL-R-SMT-1(10)")
        (field (name "AUTHOR") "CERN DEM JLC")
      )
      (libsource (lib "") (part "Coax_1Male_1Shield_1"))
    )
    (comp (ref "J31")
      (value "U.FL")
      (footprint "HIROSE_U.FL-R-SMT-1(10)")
      (fields
        (field (name "MANUFACTURER PART NUMBER") "U.FL-R-SMT-1(10)")
        (field (name "MANUFACTURER") "HIROSE (HRS)")
        (field (name "PART NUMBER") "HIROSE_U.FL-R-SMT-1(10)")
        (field (name "AUTHOR") "CERN DEM JLC")
      )
      (libsource (lib "") (part "Coax_1Male_1Shield_1"))
    )
    (comp (ref "J32")
      (value "U.FL")
      (footprint "HIROSE_U.FL-R-SMT-1(10)")
      (fields
        (field (name "MANUFACTURER PART NUMBER") "U.FL-R-SMT-1(10)")
        (field (name "MANUFACTURER") "HIROSE (HRS)")
        (field (name "PART NUMBER") "HIROSE_U.FL-R-SMT-1(10)")
        (field (name "AUTHOR") "CERN DEM JLC")
      )
      (libsource (lib "") (part "Coax_1Male_1Shield_1"))
    )
    (comp (ref "J33")
      (value "U.FL")
      (footprint "HIROSE_U.FL-R-SMT-1(10)")
      (fields
        (field (name "MANUFACTURER PART NUMBER") "U.FL-R-SMT-1(10)")
        (field (name "MANUFACTURER") "HIROSE (HRS)")
        (field (name "PART NUMBER") "HIROSE_U.FL-R-SMT-1(10)")
        (field (name "AUTHOR") "CERN DEM JLC")
      )
      (libsource (lib "Connectors") (part "Coax_1Male_1Shield"))
    )
    (comp (ref "J34")
      (value "Coax_1Female_1Shield")
      (footprint "NINIGI_MMCX-10")
      (fields
        (field (name "PART NUMBER") "MMCX-10")
        (field (name "MANUFACTURER") "NINIGI")
        (field (name "MANUFACTURER PART NUMBER") "NINIGI MMCX-10")
        (field (name "AUTHOR") "GK")
      )
      (libsource (lib "LIBRARY_SCH") (part "CON_RF_MMCX"))
    )
    (comp (ref "J35")
      (value "Coax_1Female_1Shield")
      (footprint "NINIGI_MMCX-10")
      (fields
        (field (name "PART NUMBER") "MMCX-10")
        (field (name "MANUFACTURER") "NINIGI")
        (field (name "MANUFACTURER PART NUMBER") "NINIGI MMCX-10")
        (field (name "AUTHOR") "GK")
      )
      (libsource (lib "LIBRARY_SCH") (part "CON_RF_MMCX"))
    )
    (comp (ref "L16")
      (value "120R@100MHz")
      (footprint "INDC1608X95N")
      (fields
        (field (name "MANUFACTURER PART NUMBER") "BLM18PG121SN1D")
        (field (name "MANUFACTURER") "MURATA")
        (field (name "PART NUMBER") "IND0603_MURATA_BLM18PG121SN1D")
        (field (name "AUTHOR") "CERN DEM BC")
      )
      (libsource (lib "") (part "Ferrite Bead_1"))
    )
    (comp (ref "L17")
      (value "120R@100MHz")
      (footprint "INDC1608X95N")
      (fields
        (field (name "MANUFACTURER PART NUMBER") "BLM18PG121SN1D")
        (field (name "MANUFACTURER") "MURATA")
        (field (name "PART NUMBER") "IND0603_MURATA_BLM18PG121SN1D")
        (field (name "AUTHOR") "CERN DEM BC")
      )
      (libsource (lib "Inductors & Transformers") (part "Ferrite Bead"))
    )
    (comp (ref "L18")
      (value "120R@100MHz")
      (footprint "INDC1608X95N")
      (fields
        (field (name "MANUFACTURER PART NUMBER") "BLM18PG121SN1D")
        (field (name "MANUFACTURER") "MURATA")
        (field (name "PART NUMBER") "IND0603_MURATA_BLM18PG121SN1D")
        (field (name "AUTHOR") "CERN DEM BC")
      )
      (libsource (lib "Inductors & Transformers") (part "Ferrite Bead"))
    )
    (comp (ref "L19")
      (value "120R@100MHz")
      (footprint "INDC1608X95N")
      (fields
        (field (name "MANUFACTURER PART NUMBER") "BLM18PG121SN1D")
        (field (name "MANUFACTURER") "MURATA")
        (field (name "PART NUMBER") "IND0603_MURATA_BLM18PG121SN1D")
        (field (name "AUTHOR") "CERN DEM BC")
      )
      (libsource (lib "Inductors & Transformers") (part "Ferrite Bead"))
    )
    (comp (ref "L20")
      (value "120R@100MHz")
      (footprint "INDC1608X95N")
      (fields
        (field (name "MANUFACTURER PART NUMBER") "BLM18PG121SN1D")
        (field (name "MANUFACTURER") "MURATA")
        (field (name "PART NUMBER") "IND0603_MURATA_BLM18PG121SN1D")
        (field (name "AUTHOR") "CERN DEM BC")
      )
      (libsource (lib "Inductors & Transformers") (part "Ferrite Bead"))
    )
    (comp (ref "OSC4")
      (value "0.2-250M")
      (footprint "OSC_SILICON-LAB_SI549")
      (fields
        (field (name "MANUFACTURER PART NUMBER") "549CBAC000112ABG")
        (field (name "MANUFACTURER") "Silabs")
        (field (name "PART NUMBER") "OSC_0.2_250M_SILICON-LAB_549CBAC000112ABG")
      )
      (libsource (lib "LIBRARY_SCH") (part "OSC_SILICON-LAB_SI549"))
    )
    (comp (ref "OSC5")
      (value "0.2-250M")
      (footprint "OSC_SILICON-LAB_SI549")
      (fields
        (field (name "MANUFACTURER PART NUMBER") "549CBAC000112ABG")
        (field (name "MANUFACTURER") "Silabs")
        (field (name "PART NUMBER") "OSC_0.2_250M_SILICON-LAB_549CBAC000112ABG")
      )
      (libsource (lib "LIBRARY_SCH") (part "OSC_SILICON-LAB_SI549"))
    )
    (comp (ref "Q3")
      (value "114.285MHZ")
      (footprint "XTAL_CONNOR_CS")
      (description "Crystal 4 pins 1=XTAL Control 2=GND3=XTAL 4=GND")
      (fields
        (field (name "MANUFACTURER PART NUMBER") "CS-023-114.285M")
        (field (name "MANUFACTURER") "CONNOR-WINFIELD")
        (field (name "AUTHOR") "CERN DEM JLC")
      )
      (libsource (lib "ICs And Semiconductors") (part "Quartz Crystal 1X 2GND 3X 4GND"))
    )
    (comp (ref "R67")
      (value "200")
      (footprint "RESC1005X40N")
      (description "Resistor - 1%")
      (fields
        (field (name "MANUFACTURER PART NUMBER") "R0402_200R_1%_0.0625W_100PPM")
        (field (name "MANUFACTURER") "GENERIC")
        (field (name "AUTHOR") "CERN DEM JLC")
      )
      (libsource (lib "Resistors") (part "Resistor - 1%"))
    )
    (comp (ref "R230")
      (value "200")
      (footprint "RESC1005X40N")
      (description "Resistor - 1%")
      (fields
        (field (name "MANUFACTURER PART NUMBER") "R0402_200R_1%_0.0625W_100PPM")
        (field (name "MANUFACTURER") "GENERIC")
        (field (name "AUTHOR") "CERN DEM JLC")
      )
      (libsource (lib "Resistors") (part "Resistor - 1%"))
    )
    (comp (ref "R231")
      (value "49R9")
      (footprint "RESC1005X40N")
      (description "Resistor - 1%")
      (fields
        (field (name "MANUFACTURER PART NUMBER") "R0402_49R9_1%_0.0625W_100PPM")
        (field (name "MANUFACTURER") "GENERIC")
        (field (name "AUTHOR") "CERN DEM JLC")
      )
      (libsource (lib "Resistors") (part "Resistor - 1%"))
    )
    (comp (ref "R294")
      (value "Undefined")
      (footprint "RESC1005X40N")
      (description "Resistor")
      (fields
        (field (name "MANUFACTURER PART NUMBER") "R0402_NO-VALUE")
        (field (name "AUTHOR") "CERN DEM JLC")
      )
      (libsource (lib "Resistors") (part "Resistor"))
    )
    (comp (ref "R295")
      (value "Undefined")
      (footprint "RESC1005X40N")
      (description "Resistor")
      (fields
        (field (name "MANUFACTURER PART NUMBER") "R0402_NO-VALUE")
        (field (name "AUTHOR") "CERN DEM JLC")
      )
      (libsource (lib "Resistors") (part "Resistor"))
    )
    (comp (ref "R296")
      (value "49R9")
      (footprint "RESC1005X40N")
      (description "Resistor - 1%")
      (fields
        (field (name "MANUFACTURER PART NUMBER") "R0402_49R9_1%_0.0625W_100PPM")
        (field (name "MANUFACTURER") "GENERIC")
        (field (name "AUTHOR") "CERN DEM JLC")
      )
      (libsource (lib "Resistors") (part "Resistor - 1%"))
    )
    (comp (ref "R297")
      (value "49R9")
      (footprint "RESC1005X40N")
      (description "Resistor - 1%")
      (fields
        (field (name "MANUFACTURER PART NUMBER") "R0402_49R9_1%_0.0625W_100PPM")
        (field (name "MANUFACTURER") "GENERIC")
        (field (name "AUTHOR") "CERN DEM JLC")
      )
      (libsource (lib "Resistors") (part "Resistor - 1%"))
    )
    (comp (ref "R313")
      (value "200")
      (footprint "RESC1005X40N")
      (description "Resistor - 1%")
      (fields
        (field (name "MANUFACTURER PART NUMBER") "R0402_200R_1%_0.0625W_100PPM")
        (field (name "MANUFACTURER") "GENERIC")
        (field (name "AUTHOR") "CERN DEM JLC")
      )
      (libsource (lib "Resistors") (part "Resistor - 1%"))
    )
    (comp (ref "R326")
      (value "49R9")
      (footprint "RESC1005X40N")
      (description "Resistor - 1%")
      (fields
        (field (name "MANUFACTURER PART NUMBER") "R0402_49R9_1%_0.0625W_100PPM")
        (field (name "MANUFACTURER") "GENERIC")
        (field (name "AUTHOR") "CERN DEM JLC")
      )
      (libsource (lib "Resistors") (part "Resistor - 1%"))
    )
    (comp (ref "R327")
      (value "200")
      (footprint "RESC1005X40N")
      (description "Resistor - 1%")
      (fields
        (field (name "MANUFACTURER PART NUMBER") "R0402_200R_1%_0.0625W_100PPM")
        (field (name "MANUFACTURER") "GENERIC")
        (field (name "AUTHOR") "CERN DEM JLC")
      )
      (libsource (lib "Resistors") (part "Resistor - 1%"))
    )
    (comp (ref "R328")
      (value "49R9")
      (footprint "RESC1005X40N")
      (description "Resistor - 1%")
      (fields
        (field (name "MANUFACTURER PART NUMBER") "R0402_49R9_1%_0.0625W_100PPM")
        (field (name "MANUFACTURER") "GENERIC")
        (field (name "AUTHOR") "CERN DEM JLC")
      )
      (libsource (lib "Resistors") (part "Resistor - 1%"))
    )
    (comp (ref "R329")
      (value "200")
      (footprint "RESC1005X40N")
      (description "Resistor - 1%")
      (fields
        (field (name "MANUFACTURER PART NUMBER") "R0402_200R_1%_0.0625W_100PPM")
        (field (name "MANUFACTURER") "GENERIC")
        (field (name "AUTHOR") "CERN DEM JLC")
      )
      (libsource (lib "Resistors") (part "Resistor - 1%"))
    )
    (comp (ref "R330")
      (value "49R9")
      (footprint "RESC1005X40N")
      (description "Resistor - 1%")
      (fields
        (field (name "MANUFACTURER PART NUMBER") "R0402_49R9_1%_0.0625W_100PPM")
        (field (name "MANUFACTURER") "GENERIC")
        (field (name "AUTHOR") "CERN DEM JLC")
      )
      (libsource (lib "Resistors") (part "Resistor - 1%"))
    )
    (comp (ref "R331")
      (value "200")
      (footprint "RESC1005X40N")
      (description "Resistor - 1%")
      (fields
        (field (name "MANUFACTURER PART NUMBER") "R0402_200R_1%_0.0625W_100PPM")
        (field (name "MANUFACTURER") "GENERIC")
        (field (name "AUTHOR") "CERN DEM JLC")
      )
      (libsource (lib "Resistors") (part "Resistor - 1%"))
    )
    (comp (ref "R332")
      (value "49R9")
      (footprint "RESC1005X40N")
      (description "Resistor - 1%")
      (fields
        (field (name "MANUFACTURER PART NUMBER") "R0402_49R9_1%_0.0625W_100PPM")
        (field (name "MANUFACTURER") "GENERIC")
        (field (name "AUTHOR") "CERN DEM JLC")
      )
      (libsource (lib "Resistors") (part "Resistor - 1%"))
    )
    (comp (ref "R333")
      (value "200")
      (footprint "RESC1005X40N")
      (description "Resistor - 1%")
      (fields
        (field (name "MANUFACTURER PART NUMBER") "R0402_200R_1%_0.0625W_100PPM")
        (field (name "MANUFACTURER") "GENERIC")
        (field (name "AUTHOR") "CERN DEM JLC")
      )
      (libsource (lib "Resistors") (part "Resistor - 1%"))
    )
    (comp (ref "R334")
      (value "49R9")
      (footprint "RESC1005X40N")
      (description "Resistor - 1%")
      (fields
        (field (name "MANUFACTURER PART NUMBER") "R0402_49R9_1%_0.0625W_100PPM")
        (field (name "MANUFACTURER") "GENERIC")
        (field (name "AUTHOR") "CERN DEM JLC")
      )
      (libsource (lib "Resistors") (part "Resistor - 1%"))
    )
    (comp (ref "R336")
      (value "200")
      (footprint "RESC1005X40N")
      (description "Resistor - 1%")
      (fields
        (field (name "MANUFACTURER PART NUMBER") "R0402_200R_1%_0.0625W_100PPM")
        (field (name "MANUFACTURER") "GENERIC")
        (field (name "AUTHOR") "CERN DEM JLC")
      )
      (libsource (lib "Resistors") (part "Resistor - 1%"))
    )
    (comp (ref "R341")
      (value "49R9")
      (footprint "RESC1005X40N")
      (description "Resistor - 1%")
      (fields
        (field (name "MANUFACTURER PART NUMBER") "R0402_49R9_1%_0.0625W_100PPM")
        (field (name "MANUFACTURER") "GENERIC")
        (field (name "AUTHOR") "CERN DEM JLC")
      )
      (libsource (lib "Resistors") (part "Resistor - 1%"))
    )
    (comp (ref "R342")
      (value "200")
      (footprint "RESC1005X40N")
      (description "Resistor - 1%")
      (fields
        (field (name "MANUFACTURER PART NUMBER") "R0402_200R_1%_0.0625W_100PPM")
        (field (name "MANUFACTURER") "GENERIC")
        (field (name "AUTHOR") "CERN DEM JLC")
      )
      (libsource (lib "Resistors") (part "Resistor - 1%"))
    )
    (comp (ref "R343")
      (value "49R9")
      (footprint "RESC1005X40N")
      (description "Resistor - 1%")
      (fields
        (field (name "MANUFACTURER PART NUMBER") "R0402_49R9_1%_0.0625W_100PPM")
        (field (name "MANUFACTURER") "GENERIC")
        (field (name "AUTHOR") "CERN DEM JLC")
      )
      (libsource (lib "Resistors") (part "Resistor - 1%"))
    )
    (comp (ref "R356")
      (value "100")
      (footprint "RESC1005X40N")
      (description "Resistor - 1%")
      (fields
        (field (name "MANUFACTURER PART NUMBER") "R0402_100R_1%_0.0625W_100PPM")
        (field (name "MANUFACTURER") "GENERIC")
        (field (name "AUTHOR") "CERN DEM JLC")
      )
      (libsource (lib "Resistors") (part "Resistor - 1%"))
    )
    (comp (ref "R357")
      (value "4k7")
      (footprint "RESC1005X40N")
      (description "Resistor - 1%")
      (fields
        (field (name "MANUFACTURER PART NUMBER") "R0402_4K7_1%_0.0625W_100PPM")
        (field (name "MANUFACTURER") "GENERIC")
        (field (name "AUTHOR") "CERN DEM JLC")
      )
      (libsource (lib "Resistors") (part "Resistor - 1%"))
    )
    (comp (ref "R358")
      (value "100")
      (footprint "RESC1005X40N")
      (description "Resistor - 1%")
      (fields
        (field (name "MANUFACTURER PART NUMBER") "R0402_100R_1%_0.0625W_100PPM")
        (field (name "MANUFACTURER") "GENERIC")
        (field (name "AUTHOR") "CERN DEM JLC")
      )
      (libsource (lib "Resistors") (part "Resistor - 1%"))
    )
    (comp (ref "R359")
      (value "200")
      (footprint "RESC1005X40N")
      (description "Resistor - 1%")
      (fields
        (field (name "MANUFACTURER PART NUMBER") "R0402_200R_1%_0.0625W_100PPM")
        (field (name "MANUFACTURER") "GENERIC")
        (field (name "AUTHOR") "CERN DEM JLC")
      )
      (libsource (lib "Resistors") (part "Resistor - 1%"))
    )
    (comp (ref "R360")
      (value "200")
      (footprint "RESC1005X40N")
      (description "Resistor - 1%")
      (fields
        (field (name "MANUFACTURER PART NUMBER") "R0402_200R_1%_0.0625W_100PPM")
        (field (name "MANUFACTURER") "GENERIC")
        (field (name "AUTHOR") "CERN DEM JLC")
      )
      (libsource (lib "Resistors") (part "Resistor - 1%"))
    )
    (comp (ref "R361")
      (value "4k7")
      (footprint "RESC1005X40N")
      (description "Resistor - 1%")
      (fields
        (field (name "MANUFACTURER PART NUMBER") "R0402_4K7_1%_0.0625W_100PPM")
        (field (name "MANUFACTURER") "GENERIC")
        (field (name "AUTHOR") "CERN DEM JLC")
      )
      (libsource (lib "Resistors") (part "Resistor - 1%"))
    )
    (comp (ref "R362")
      (value "4k7")
      (footprint "RESC1005X40N")
      (description "Resistor - 1%")
      (fields
        (field (name "MANUFACTURER PART NUMBER") "R0402_4K7_1%_0.0625W_100PPM")
        (field (name "MANUFACTURER") "GENERIC")
        (field (name "AUTHOR") "CERN DEM JLC")
      )
      (libsource (lib "Resistors") (part "Resistor - 1%"))
    )
    (comp (ref "R363")
      (value "200")
      (footprint "RESC1005X40N")
      (description "Resistor - 1%")
      (fields
        (field (name "MANUFACTURER PART NUMBER") "R0402_200R_1%_0.0625W_100PPM")
        (field (name "MANUFACTURER") "GENERIC")
        (field (name "AUTHOR") "CERN DEM JLC")
      )
      (libsource (lib "Resistors") (part "Resistor - 1%"))
    )
    (comp (ref "R364")
      (value "4k7")
      (footprint "RESC1005X40N")
      (description "Resistor - 1%")
      (fields
        (field (name "MANUFACTURER PART NUMBER") "R0402_4K7_1%_0.0625W_100PPM")
        (field (name "MANUFACTURER") "GENERIC")
        (field (name "AUTHOR") "CERN DEM JLC")
      )
      (libsource (lib "Resistors") (part "Resistor - 1%"))
    )
    (comp (ref "R365")
      (value "4k7")
      (footprint "RESC1005X40N")
      (description "Resistor - 1%")
      (fields
        (field (name "MANUFACTURER PART NUMBER") "R0402_4K7_1%_0.0625W_100PPM")
        (field (name "MANUFACTURER") "GENERIC")
        (field (name "AUTHOR") "CERN DEM JLC")
      )
      (libsource (lib "Resistors") (part "Resistor - 1%"))
    )
    (comp (ref "R366")
      (value "200")
      (footprint "RESC1005X40N")
      (description "Resistor - 1%")
      (fields
        (field (name "MANUFACTURER PART NUMBER") "R0402_200R_1%_0.0625W_100PPM")
        (field (name "MANUFACTURER") "GENERIC")
        (field (name "AUTHOR") "CERN DEM JLC")
      )
      (libsource (lib "Resistors") (part "Resistor - 1%"))
    )
    (comp (ref "R367")
      (value "200")
      (footprint "RESC1005X40N")
      (description "Resistor - 1%")
      (fields
        (field (name "MANUFACTURER PART NUMBER") "R0402_200R_1%_0.0625W_100PPM")
        (field (name "MANUFACTURER") "GENERIC")
        (field (name "AUTHOR") "CERN DEM JLC")
      )
      (libsource (lib "Resistors") (part "Resistor - 1%"))
    )
    (comp (ref "R368")
      (value "200")
      (footprint "RESC1005X40N")
      (description "Resistor - 1%")
      (fields
        (field (name "MANUFACTURER PART NUMBER") "R0402_200R_1%_0.0625W_100PPM")
        (field (name "MANUFACTURER") "GENERIC")
        (field (name "AUTHOR") "CERN DEM JLC")
      )
      (libsource (lib "Resistors") (part "Resistor - 1%"))
    )
    (comp (ref "R369")
      (value "200")
      (footprint "RESC1005X40N")
      (description "Resistor - 1%")
      (fields
        (field (name "MANUFACTURER PART NUMBER") "R0402_200R_1%_0.0625W_100PPM")
        (field (name "MANUFACTURER") "GENERIC")
        (field (name "AUTHOR") "CERN DEM JLC")
      )
      (libsource (lib "Resistors") (part "Resistor - 1%"))
    )
    (comp (ref "R370")
      (value "200")
      (footprint "RESC1005X40N")
      (description "Resistor - 1%")
      (fields
        (field (name "MANUFACTURER PART NUMBER") "R0402_200R_1%_0.0625W_100PPM")
        (field (name "MANUFACTURER") "GENERIC")
        (field (name "AUTHOR") "CERN DEM JLC")
      )
      (libsource (lib "Resistors") (part "Resistor - 1%"))
    )
    (comp (ref "R371")
      (value "200")
      (footprint "RESC1005X40N")
      (description "Resistor - 1%")
      (fields
        (field (name "MANUFACTURER PART NUMBER") "R0402_200R_1%_0.0625W_100PPM")
        (field (name "MANUFACTURER") "GENERIC")
        (field (name "AUTHOR") "CERN DEM JLC")
      )
      (libsource (lib "Resistors") (part "Resistor - 1%"))
    )
    (comp (ref "R372")
      (value "0")
      (footprint "RESC1005X40N")
      (description "Resistor")
      (fields
        (field (name "MANUFACTURER PART NUMBER") "R0402_0R_JUMPER")
        (field (name "MANUFACTURER") "GENERIC")
        (field (name "AUTHOR") "CERN DEM JLC")
      )
      (libsource (lib "Resistors") (part "Resistor"))
    )
    (comp (ref "R373")
      (value "200")
      (footprint "RESC1005X40N")
      (description "Resistor - 1%")
      (fields
        (field (name "MANUFACTURER PART NUMBER") "R0402_200R_1%_0.0625W_100PPM")
        (field (name "MANUFACTURER") "GENERIC")
        (field (name "AUTHOR") "CERN DEM JLC")
      )
      (libsource (lib "Resistors") (part "Resistor - 1%"))
    )
    (comp (ref "R374")
      (value "200")
      (footprint "RESC1005X40N")
      (description "Resistor - 1%")
      (fields
        (field (name "MANUFACTURER PART NUMBER") "R0402_200R_1%_0.0625W_100PPM")
        (field (name "MANUFACTURER") "GENERIC")
        (field (name "AUTHOR") "CERN DEM JLC")
      )
      (libsource (lib "Resistors") (part "Resistor - 1%"))
    )
    (comp (ref "R375")
      (value "0")
      (footprint "RESC1005X40N")
      (description "Resistor")
      (fields
        (field (name "MANUFACTURER PART NUMBER") "R0402_0R_JUMPER")
        (field (name "MANUFACTURER") "GENERIC")
        (field (name "AUTHOR") "CERN DEM JLC")
      )
      (libsource (lib "Resistors") (part "Resistor"))
    )
    (comp (ref "R376")
      (value "49R9")
      (footprint "RESC1005X40N")
      (description "Resistor - 1%")
      (fields
        (field (name "MANUFACTURER PART NUMBER") "R0402_49R9_1%_0.0625W_100PPM")
        (field (name "MANUFACTURER") "GENERIC")
        (field (name "AUTHOR") "CERN DEM JLC")
      )
      (libsource (lib "Resistors") (part "Resistor - 1%"))
    )
    (comp (ref "R377")
      (value "150")
      (footprint "RESC1005X40N")
      (description "Resistor - 1%")
      (fields
        (field (name "MANUFACTURER PART NUMBER") "R0402_150R_1%_0.0625W_100PPM")
        (field (name "MANUFACTURER") "GENERIC")
        (field (name "AUTHOR") "CERN DEM JLC")
      )
      (libsource (lib "Resistors") (part "Resistor - 1%"))
    )
    (comp (ref "R378")
      (value "200")
      (footprint "RESC1005X40N")
      (description "Resistor - 1%")
      (fields
        (field (name "MANUFACTURER PART NUMBER") "R0402_200R_1%_0.0625W_100PPM")
        (field (name "MANUFACTURER") "GENERIC")
        (field (name "AUTHOR") "CERN DEM JLC")
      )
      (libsource (lib "Resistors") (part "Resistor - 1%"))
    )
    (comp (ref "R379")
      (value "0")
      (footprint "RESC1005X40N")
      (description "Resistor")
      (fields
        (field (name "MANUFACTURER PART NUMBER") "R0402_0R_JUMPER")
        (field (name "MANUFACTURER") "GENERIC")
        (field (name "AUTHOR") "CERN DEM JLC")
      )
      (libsource (lib "Resistors") (part "Resistor"))
    )
    (comp (ref "R380")
      (value "0")
      (footprint "RESC1005X40N")
      (description "Resistor")
      (fields
        (field (name "MANUFACTURER PART NUMBER") "R0402_0R_JUMPER")
        (field (name "MANUFACTURER") "GENERIC")
        (field (name "AUTHOR") "CERN DEM JLC")
      )
      (libsource (lib "Resistors") (part "Resistor"))
    )
    (comp (ref "R381")
      (value "200")
      (footprint "RESC1005X40N")
      (description "Resistor - 1%")
      (fields
        (field (name "MANUFACTURER PART NUMBER") "R0402_200R_1%_0.0625W_100PPM")
        (field (name "MANUFACTURER") "GENERIC")
        (field (name "AUTHOR") "CERN DEM JLC")
      )
      (libsource (lib "Resistors") (part "Resistor - 1%"))
    )
    (comp (ref "R382")
      (value "0")
      (footprint "RESC1005X40N")
      (description "Resistor")
      (fields
        (field (name "MANUFACTURER PART NUMBER") "R0402_0R_JUMPER")
        (field (name "MANUFACTURER") "GENERIC")
        (field (name "AUTHOR") "CERN DEM JLC")
      )
      (libsource (lib "Resistors") (part "Resistor"))
    )
    (comp (ref "R383")
      (value "0")
      (footprint "RESC1005X40N")
      (description "Resistor")
      (fields
        (field (name "MANUFACTURER PART NUMBER") "R0402_0R_JUMPER")
        (field (name "MANUFACTURER") "GENERIC")
        (field (name "AUTHOR") "CERN DEM JLC")
      )
      (libsource (lib "Resistors") (part "Resistor"))
    )
    (comp (ref "R384")
      (value "0")
      (footprint "RESC1005X40N")
      (description "Resistor")
      (fields
        (field (name "MANUFACTURER PART NUMBER") "R0402_0R_JUMPER")
        (field (name "MANUFACTURER") "GENERIC")
        (field (name "AUTHOR") "CERN DEM JLC")
      )
      (libsource (lib "Resistors") (part "Resistor"))
    )
    (comp (ref "R385")
      (value "0")
      (footprint "RESC1005X40N")
      (description "Resistor")
      (fields
        (field (name "MANUFACTURER PART NUMBER") "R0402_0R_JUMPER")
        (field (name "MANUFACTURER") "GENERIC")
        (field (name "AUTHOR") "CERN DEM JLC")
      )
      (libsource (lib "Resistors") (part "Resistor"))
    )
    (comp (ref "R386")
      (value "0")
      (footprint "RESC1005X40N")
      (description "Resistor")
      (fields
        (field (name "MANUFACTURER PART NUMBER") "R0402_0R_JUMPER")
        (field (name "MANUFACTURER") "GENERIC")
        (field (name "AUTHOR") "CERN DEM JLC")
      )
      (libsource (lib "Resistors") (part "Resistor"))
    )
    (comp (ref "R531")
      (value "49R9")
      (footprint "RESC1005X40N")
      (description "Resistor - 1%")
      (fields
        (field (name "MANUFACTURER PART NUMBER") "R0402_49R9_1%_0.0625W_100PPM")
        (field (name "MANUFACTURER") "GENERIC")
        (field (name "AUTHOR") "CERN DEM JLC")
      )
      (libsource (lib "Resistors") (part "Resistor - 1%"))
    )
    (comp (ref "R532")
      (value "49R9")
      (footprint "RESC1005X40N")
      (description "Resistor - 1%")
      (fields
        (field (name "MANUFACTURER PART NUMBER") "R0402_49R9_1%_0.0625W_100PPM")
        (field (name "MANUFACTURER") "GENERIC")
        (field (name "AUTHOR") "CERN DEM JLC")
      )
      (libsource (lib "Resistors") (part "Resistor - 1%"))
    )
    (comp (ref "R533")
      (value "49R9")
      (footprint "RESC1005X40N")
      (description "Resistor - 1%")
      (fields
        (field (name "MANUFACTURER PART NUMBER") "R0402_49R9_1%_0.0625W_100PPM")
        (field (name "MANUFACTURER") "GENERIC")
        (field (name "AUTHOR") "CERN DEM JLC")
      )
      (libsource (lib "Resistors") (part "Resistor - 1%"))
    )
    (comp (ref "R534")
      (value "49R9")
      (footprint "RESC1005X40N")
      (description "Resistor - 1%")
      (fields
        (field (name "MANUFACTURER PART NUMBER") "R0402_49R9_1%_0.0625W_100PPM")
        (field (name "MANUFACTURER") "GENERIC")
        (field (name "AUTHOR") "CERN DEM JLC")
      )
      (libsource (lib "Resistors") (part "Resistor - 1%"))
    )
    (comp (ref "R551")
      (value "100")
      (footprint "RESC1005X40N")
      (description "Resistor - 1%")
      (fields
        (field (name "MANUFACTURER PART NUMBER") "R0402_100R_1%_0.0625W_100PPM")
        (field (name "MANUFACTURER") "GENERIC")
        (field (name "AUTHOR") "CERN DEM JLC")
      )
      (libsource (lib "Resistors") (part "Resistor - 1%"))
    )
    (comp (ref "R552")
      (value "0")
      (footprint "RESC1005X40N")
      (description "Resistor")
      (fields
        (field (name "MANUFACTURER PART NUMBER") "R0402_0R_JUMPER")
        (field (name "MANUFACTURER") "GENERIC")
        (field (name "AUTHOR") "CERN DEM JLC")
      )
      (libsource (lib "Resistors") (part "Resistor"))
    )
    (comp (ref "R553")
      (value "0")
      (footprint "RESC1005X40N")
      (description "Resistor")
      (fields
        (field (name "MANUFACTURER PART NUMBER") "R0402_0R_JUMPER")
        (field (name "MANUFACTURER") "GENERIC")
        (field (name "AUTHOR") "CERN DEM JLC")
      )
      (libsource (lib "Resistors") (part "Resistor"))
    )
    (comp (ref "TP1")
      (value "Test Point")
      (footprint "TPS127")
      (fields (field (name "PART NUMBER") "SMD_PAD_1.27X1.27MM") (field (name "AUTHOR") "CERN DEM JLC"))
      (libsource (lib "Eletro-mechanical") (part "Test Point"))
    )
    (comp (ref "TP2")
      (value "Test Point")
      (footprint "TPS127")
      (fields (field (name "PART NUMBER") "SMD_PAD_1.27X1.27MM") (field (name "AUTHOR") "CERN DEM JLC"))
      (libsource (lib "Eletro-mechanical") (part "Test Point"))
    )
    (comp (ref "TP3")
      (value "Test Point")
      (footprint "TPS127")
      (fields (field (name "PART NUMBER") "SMD_PAD_1.27X1.27MM") (field (name "AUTHOR") "CERN DEM JLC"))
      (libsource (lib "Eletro-mechanical") (part "Test Point"))
    )
    (comp (ref "TP4")
      (value "Test Point")
      (footprint "TPS127")
      (fields (field (name "PART NUMBER") "SMD_PAD_1.27X1.27MM") (field (name "AUTHOR") "CERN DEM JLC"))
      (libsource (lib "Eletro-mechanical") (part "Test Point"))
    )
    (comp (ref "TP5")
      (value "Test Point")
      (footprint "TPS127")
      (fields (field (name "PART NUMBER") "SMD_PAD_1.27X1.27MM") (field (name "AUTHOR") "CERN DEM JLC"))
      (libsource (lib "Eletro-mechanical") (part "Test Point"))
    )
    (comp (ref "TP6")
      (value "Test Point")
      (footprint "TPS127")
      (fields (field (name "PART NUMBER") "SMD_PAD_1.27X1.27MM") (field (name "AUTHOR") "CERN DEM JLC"))
      (libsource (lib "Eletro-mechanical") (part "Test Point"))
    )
    (comp (ref "TP14")
      (value "Test Point")
      (footprint "TPS127")
      (fields (field (name "PART NUMBER") "SMD_PAD_1.27X1.27MM") (field (name "AUTHOR") "CERN DEM JLC"))
      (libsource (lib "Eletro-mechanical") (part "Test Point"))
    )
    (comp (ref "TP15")
      (value "Test Point")
      (footprint "TPS127")
      (fields (field (name "PART NUMBER") "SMD_PAD_1.27X1.27MM") (field (name "AUTHOR") "CERN DEM JLC"))
      (libsource (lib "Eletro-mechanical") (part "Test Point"))
    )
    (comp (ref "TR1")
      (value "1:2")
      (footprint "XFMR_MINI-CIRCUITS_DB1627")
      (description "50 OHMS 10 to 4000 MHz RF Transformer")
      (fields
        (field (name "PART NUMBER") "XFMR_MINI-CIRCUITS_TCM2-43X+")
        (field (name "POWER") "0.4W")
        (field (name "MANUFACTURER PART NUMBER") "TCM2-43X+")
        (field (name "AUTHOR") "CERN DEM BC")
      )
      (libsource (lib "Inductors & Transformers") (part "XFMR_MINI-CIRCUITS_TCM2-43X"))
    )
  )
  (nets
    (net (code "8") (name "/AUX_CLOCK_C2_N") (class "Default")
      (node (ref "C342") (pin "2") (pinfunction "2_2") (pintype "passive"))
      (node (ref "J35") (pin "1") (pinfunction "1_1") (pintype "bidirectional"))
      (node (ref "R358") (pin "1") (pinfunction "1_1") (pintype "passive"))
    )
    (net (code "9") (name "/AUX_CLOCK_C2_P") (class "Default")
      (node (ref "C341") (pin "2") (pinfunction "2_2") (pintype "passive"))
      (node (ref "J34") (pin "1") (pinfunction "1_1") (pintype "bidirectional"))
      (node (ref "R358") (pin "2") (pinfunction "2_2") (pintype "passive"))
    )
    (net (code "10") (name "/CDR_CLK_CLEAN0_N") (class "Default")
      (node (ref "C358") (pin "2") (pinfunction "2_2") (pintype "passive"))
    )
    (net (code "11") (name "/CDR_CLK_CLEAN0_P") (class "Default")
      (node (ref "C362") (pin "2") (pinfunction "2_2") (pintype "passive"))
    )
    (net (code "12") (name "/CDR_CLK_CLEAN1_N") (class "Default")
      (node (ref "C359") (pin "2") (pinfunction "2_2") (pintype "passive"))
    )
    (net (code "13") (name "/CDR_CLK_CLEAN1_P") (class "Default")
      (node (ref "C361") (pin "2") (pinfunction "2_2") (pintype "passive"))
    )
    (net (code "14") (name "/CDR_CLK_CLEAN2_N") (class "Default")
      (node (ref "C274") (pin "2") (pinfunction "2_2") (pintype "passive"))
    )
    (net (code "15") (name "/CDR_CLK_CLEAN2_P") (class "Default")
      (node (ref "C1") (pin "2") (pinfunction "2_2") (pintype "passive"))
    )
    (net (code "16") (name "/CDR_CLK_CLEAN3_N") (class "Default")
      (node (ref "C448") (pin "2") (pinfunction "2_2") (pintype "passive"))
    )
    (net (code "17") (name "/CDR_CLK_CLEAN3_P") (class "Default")
      (node (ref "C407") (pin "2") (pinfunction "2_2") (pintype "passive"))
    )
    (net (code "18") (name "/CDR_CLK_CLEAN4_N") (class "Default")
      (node (ref "C370") (pin "2") (pinfunction "2_2") (pintype "passive"))
      (node (ref "J27") (pin "1") (pinfunction "1_1") (pintype "bidirectional"))
    )
    (net (code "19") (name "/CDR_CLK_CLEAN4_P") (class "Default")
      (node (ref "C369") (pin "2") (pinfunction "2_2") (pintype "passive"))
      (node (ref "J28") (pin "1") (pinfunction "1_1") (pintype "bidirectional"))
    )
    (net (code "20") (name "/CLK_SEL") (class "Default")
      (node (ref "IC44") (pin "32") (pinfunction "IN_SEL_32") (pintype "input"))
    )
    (net (code "25") (name "/EN_P3V3_CLK") (class "Default")
      (node (ref "IC1") (pin "1") (pinfunction "EN_1") (pintype "power_in"))
    )
    (net (code "26") (name "/Helper_CLK_N") (class "Default")
      (node (ref "C346") (pin "2") (pinfunction "2_2") (pintype "passive"))
      (node (ref "R297") (pin "1") (pinfunction "1_1") (pintype "passive"))
      (node (ref "R375") (pin "2") (pinfunction "2_2") (pintype "passive"))
    )
    (net (code "27") (name "/Helper_CLK_P") (class "Default")
      (node (ref "C344") (pin "2") (pinfunction "2_2") (pintype "passive"))
      (node (ref "R296") (pin "1") (pinfunction "1_1") (pintype "passive"))
      (node (ref "R379") (pin "1") (pinfunction "1_1") (pintype "passive"))
      (node (ref "R386") (pin "2") (pinfunction "2_2") (pintype "passive"))
    )
    (net (code "28") (name "/Helper_DCXO_OE") (class "Default")
      (node (ref "R383") (pin "2") (pinfunction "2_2") (pintype "passive"))
      (node (ref "R385") (pin "2") (pinfunction "2_2") (pintype "passive"))
    )
    (net (code "29") (name "/Helper_DCXO_SCL") (class "Default")
      (node (ref "OSC5") (pin "8") (pinfunction "SCL_8") (pintype "passive"))
      (node (ref "R365") (pin "1") (pinfunction "1_1") (pintype "passive"))
      (node (ref "TP6") (pin "1") (pinfunction "1_1") (pintype "bidirectional"))
    )
    (net (code "30") (name "/Helper_DCXO_SDA") (class "Default")
      (node (ref "OSC5") (pin "7") (pinfunction "SDA_7") (pintype "passive"))
      (node (ref "R364") (pin "1") (pinfunction "1_1") (pintype "passive"))
      (node (ref "TP5") (pin "1") (pinfunction "1_1") (pintype "bidirectional"))
    )
    (net (code "32") (name "/Main_DCXO_N") (class "Default")
      (node (ref "C277") (pin "2") (pinfunction "2_2") (pintype "passive"))
      (node (ref "C371") (pin "2") (pinfunction "2_2") (pintype "passive"))
      (node (ref "IC44") (pin "2") (pinfunction "~{CLK0}_2") (pintype "input"))
    )
    (net (code "33") (name "/Main_DCXO_OE") (class "Default")
      (node (ref "R382") (pin "2") (pinfunction "2_2") (pintype "passive"))
      (node (ref "R384") (pin "2") (pinfunction "2_2") (pintype "passive"))
    )
    (net (code "34") (name "/Main_DCXO_P") (class "Default")
      (node (ref "C276") (pin "2") (pinfunction "2_2") (pintype "passive"))
      (node (ref "IC44") (pin "1") (pinfunction "CLK0_1") (pintype "input"))
    )
    (net (code "35") (name "/Main_DCXO_SCL") (class "Default")
      (node (ref "OSC4") (pin "8") (pinfunction "SCL_8") (pintype "passive"))
      (node (ref "R362") (pin "1") (pinfunction "1_1") (pintype "passive"))
      (node (ref "TP4") (pin "1") (pinfunction "1_1") (pintype "bidirectional"))
    )
    (net (code "36") (name "/Main_DCXO_SDA") (class "Default")
      (node (ref "OSC4") (pin "7") (pinfunction "SDA_7") (pintype "passive"))
      (node (ref "R361") (pin "1") (pinfunction "1_1") (pintype "passive"))
      (node (ref "TP3") (pin "1") (pinfunction "1_1") (pintype "bidirectional"))
    )
    (net (code "37") (name "/P3V3_CLKDIS4F") (class "Default")
      (node (ref "C365") (pin "2") (pinfunction "2_2") (pintype "passive"))
      (node (ref "C366") (pin "2") (pinfunction "2_2") (pintype "passive"))
      (node (ref "C367") (pin "2") (pinfunction "2_2") (pintype "passive"))
      (node (ref "C368") (pin "2") (pinfunction "2_2") (pintype "passive"))
      (node (ref "C513") (pin "2") (pinfunction "2_2") (pintype "passive"))
      (node (ref "C514") (pin "1") (pinfunction "1_1") (pintype "passive"))
      (node (ref "C515") (pin "2") (pinfunction "2_2") (pintype "passive"))
      (node (ref "IC44") (pin "10") (pinfunction "VCC_10") (pintype "power_in"))
      (node (ref "IC44") (pin "15") (pinfunction "VCC_15") (pintype "power_in"))
      (node (ref "IC44") (pin "16") (pinfunction "VCC_16") (pintype "power_in"))
      (node (ref "IC44") (pin "25") (pinfunction "VCC_25") (pintype "power_in"))
      (node (ref "IC44") (pin "26") (pinfunction "VCC_26") (pintype "power_in"))
      (node (ref "IC44") (pin "31") (pinfunction "VCC_31") (pintype "power_in"))
      (node (ref "L20") (pin "2") (pinfunction "2_2") (pintype "passive"))
    )
    (net (code "38") (name "/P5V0_LDO_IN") (class "Default")
      (node (ref "C656") (pin "2") (pinfunction "2_2") (pintype "passive"))
      (node (ref "IC1") (pin "2") (pinfunction "IN_2") (pintype "input"))
      (node (ref "L17") (pin "2") (pinfunction "2_2") (pintype "passive"))
    )
    (net (code "39") (name "/REC_CLOCK_C_N") (class "Default")
      (node (ref "C340") (pin "2") (pinfunction "2_2") (pintype "passive"))
      (node (ref "R356") (pin "1") (pinfunction "1_1") (pintype "passive"))
    )
    (net (code "40") (name "/REC_CLOCK_C_P") (class "Default")
      (node (ref "C339") (pin "2") (pinfunction "2_2") (pintype "passive"))
      (node (ref "R356") (pin "2") (pinfunction "2_2") (pintype "passive"))
    )
    (net (code "41") (name "/REC_CLOCK_N") (class "Default")
      (node (ref "C340") (pin "1") (pinfunction "1_1") (pintype "passive"))
      (node (ref "IC43") (pin "17") (pinfunction "CKIN1-_17") (pintype "input"))
    )
    (net (code "42") (name "/REC_CLOCK_P") (class "Default")
      (node (ref "C339") (pin "1") (pinfunction "1_1") (pintype "passive"))
      (node (ref "IC43") (pin "16") (pinfunction "CKIN1+_16") (pintype "input"))
    )
    (net (code "43") (name "/REF_LOC_N") (class "Default")
      (node (ref "C267") (pin "2") (pinfunction "2_2") (pintype "passive"))
      (node (ref "C268") (pin "2") (pinfunction "2_2") (pintype "passive"))
      (node (ref "IC44") (pin "6") (pinfunction "~{CLK1}_6") (pintype "input"))
    )
    (net (code "44") (name "/REF_LOC_P") (class "Default")
      (node (ref "C265") (pin "2") (pinfunction "2_2") (pintype "passive"))
      (node (ref "C266") (pin "2") (pinfunction "2_2") (pintype "passive"))
      (node (ref "IC44") (pin "5") (pinfunction "CLK1_5") (pintype "input"))
    )
    (net (code "45") (name "/RF_OUT") (class "Default")
      (node (ref "C364") (pin "2") (pinfunction "2_2") (pintype "passive"))
    )
    (net (code "46") (name "/SI5324_INT_ALM") (class "Default")
      (node (ref "IC43") (pin "3") (pinfunction "INT_C1B_3") (pintype "output"))
    )
    (net (code "47") (name "/SI5324_RST") (class "Default")
      (node (ref "IC43") (pin "1") (pinfunction "~{RST}_1") (pintype "input"))
    )
    (net (code "48") (name "/SI5324_SCL") (class "Default")
      (node (ref "IC43") (pin "22") (pinfunction "SCL_22") (pintype "input"))
      (node (ref "TP2") (pin "1") (pinfunction "1_1") (pintype "bidirectional"))
    )
    (net (code "49") (name "/SI5324_SDA") (class "Default")
      (node (ref "IC43") (pin "23") (pinfunction "SDA_SDO_23") (pintype "bidirectional"))
      (node (ref "TP1") (pin "1") (pinfunction "1_1") (pintype "bidirectional"))
    )
    (net (code "50") (name "/SI5324_VDD") (class "Default")
      (node (ref "C337") (pin "2") (pinfunction "2_2") (pintype "passive"))
      (node (ref "C338") (pin "2") (pinfunction "2_2") (pintype "passive"))
      (node (ref "C345") (pin "2") (pinfunction "2_2") (pintype "passive"))
      (node (ref "C512") (pin "1") (pinfunction "1_1") (pintype "passive"))
      (node (ref "IC43") (pin "10") (pinfunction "VDD_10") (pintype "power_in"))
      (node (ref "IC43") (pin "32") (pinfunction "VDD_32") (pintype "power_in"))
      (node (ref "IC43") (pin "5") (pinfunction "VDD_5") (pintype "power_in"))
      (node (ref "L16") (pin "2") (pinfunction "2_2") (pintype "passive"))
    )
    (net (code "51") (name "/SI5324_XTAL_XA") (class "Default")
      (node (ref "IC43") (pin "6") (pinfunction "XA_6") (pintype "input"))
      (node (ref "Q3") (pin "3") (pinfunction "X_3") (pintype "passive"))
    )
    (net (code "52") (name "/SI5324_XTAL_XB") (class "Default")
      (node (ref "IC43") (pin "7") (pinfunction "XB_7") (pintype "input"))
      (node (ref "Q3") (pin "1") (pinfunction "X_1") (pintype "passive"))
    )
    (net (code "53") (name "/TCLKA_N") (class "Default")
      (node (ref "C268") (pin "1") (pinfunction "1_1") (pintype "passive"))
    )
    (net (code "54") (name "/TCLKA_P") (class "Default")
      (node (ref "C265") (pin "1") (pinfunction "1_1") (pintype "passive"))
    )
    (net (code "55") (name "/TCLKB_N") (class "Default")
      (node (ref "C272") (pin "1") (pinfunction "1_1") (pintype "passive"))
      (node (ref "C376") (pin "2") (pinfunction "2_2") (pintype "passive"))
    )
    (net (code "56") (name "/TCLKB_P") (class "Default")
      (node (ref "C270") (pin "1") (pinfunction "1_1") (pintype "passive"))
      (node (ref "C375") (pin "2") (pinfunction "2_2") (pintype "passive"))
    )
    (net (code "61") (name "GND") (class "Default")
      (node (ref "C337") (pin "1") (pinfunction "1_1") (pintype "passive"))
      (node (ref "C338") (pin "1") (pinfunction "1_1") (pintype "passive"))
      (node (ref "C345") (pin "1") (pinfunction "1_1") (pintype "passive"))
      (node (ref "C350") (pin "1") (pinfunction "1_1") (pintype "passive"))
      (node (ref "C351") (pin "1") (pinfunction "1_1") (pintype "passive"))
      (node (ref "C356") (pin "1") (pinfunction "1_1") (pintype "passive"))
      (node (ref "C357") (pin "1") (pinfunction "1_1") (pintype "passive"))
      (node (ref "C360") (pin "1") (pinfunction "1_1") (pintype "passive"))
      (node (ref "C363") (pin "1") (pinfunction "1_1") (pintype "passive"))
      (node (ref "C365") (pin "1") (pinfunction "1_1") (pintype "passive"))
      (node (ref "C366") (pin "1") (pinfunction "1_1") (pintype "passive"))
      (node (ref "C367") (pin "1") (pinfunction "1_1") (pintype "passive"))
      (node (ref "C368") (pin "1") (pinfunction "1_1") (pintype "passive"))
      (node (ref "C371") (pin "1") (pinfunction "1_1") (pintype "passive"))
      (node (ref "C372") (pin "1") (pinfunction "1_1") (pintype "passive"))
      (node (ref "C373") (pin "2") (pinfunction "2_2") (pintype "passive"))
      (node (ref "C374") (pin "2") (pinfunction "2_2") (pintype "passive"))
      (node (ref "C377") (pin "1") (pinfunction "1_1") (pintype "passive"))
      (node (ref "C512") (pin "2") (pinfunction "2_2") (pintype "passive"))
      (node (ref "C513") (pin "1") (pinfunction "1_1") (pintype "passive"))
      (node (ref "C514") (pin "2") (pinfunction "2_2") (pintype "passive"))
      (node (ref "C515") (pin "1") (pinfunction "1_1") (pintype "passive"))
      (node (ref "C531") (pin "1") (pinfunction "1_1") (pintype "passive"))
      (node (ref "C654") (pin "1") (pinfunction "1_1") (pintype "passive"))
      (node (ref "C655") (pin "1") (pinfunction "1_1") (pintype "passive"))
      (node (ref "C656") (pin "1") (pinfunction "1_1") (pintype "passive"))
      (node (ref "C657") (pin "1") (pinfunction "1_1") (pintype "passive"))
      (node (ref "C658") (pin "1") (pinfunction "1_1") (pintype "passive"))
      (node (ref "IC1") (pin "3") (pinfunction "GND_3") (pintype "power_in"))
      (node (ref "IC1") (pin "6") (pinfunction "GND_6") (pintype "power_in"))
      (node (ref "IC43") (pin "19") (pinfunction "GND_19") (pintype "power_in"))
      (node (ref "IC43") (pin "20") (pinfunction "GND_20") (pintype "power_in"))
      (node (ref "IC43") (pin "24") (pinfunction "A0_24") (pintype "input"))
      (node (ref "IC43") (pin "25") (pinfunction "A1_25") (pintype "input"))
      (node (ref "IC43") (pin "26") (pinfunction "A2_~{SS}_26") (pintype "input"))
      (node (ref "IC43") (pin "31") (pinfunction "GND_31") (pintype "power_in"))
      (node (ref "IC43") (pin "36") (pinfunction "CMODE_36") (pintype "input"))
      (node (ref "IC43") (pin "37") (pinfunction "GND_37") (pintype "power_in"))
      (node (ref "IC43") (pin "8") (pinfunction "GND_8") (pintype "power_in"))
      (node (ref "IC44") (pin "33") (pinfunction "VEE_33") (pintype "power_in"))
      (node (ref "J15") (pin "2") (pinfunction "2_2") (pintype "bidirectional"))
      (node (ref "J19") (pin "2") (pinfunction "2_2") (pintype "bidirectional"))
      (node (ref "J20") (pin "2") (pinfunction "2_2") (pintype "bidirectional"))
      (node (ref "J27") (pin "2") (pinfunction "2_2") (pintype "bidirectional"))
      (node (ref "J28") (pin "2") (pinfunction "2_2") (pintype "bidirectional"))
      (node (ref "J31") (pin "2") (pinfunction "2_2") (pintype "bidirectional"))
      (node (ref "J32") (pin "2") (pinfunction "2_2") (pintype "bidirectional"))
      (node (ref "J33") (pin "2") (pinfunction "2_2") (pintype "bidirectional"))
      (node (ref "J34") (pin "2") (pinfunction "2_2") (pintype "bidirectional"))
      (node (ref "J35") (pin "2") (pinfunction "2_2") (pintype "bidirectional"))
      (node (ref "OSC4") (pin "3") (pinfunction "GND_3") (pintype "passive"))
      (node (ref "OSC5") (pin "3") (pinfunction "GND_3") (pintype "passive"))
      (node (ref "Q3") (pin "2") (pinfunction "GND_2") (pintype "power_in"))
      (node (ref "Q3") (pin "4") (pinfunction "GND_4") (pintype "power_in"))
      (node (ref "R230") (pin "2") (pinfunction "2_2") (pintype "passive"))
      (node (ref "R295") (pin "1") (pinfunction "1_1") (pintype "passive"))
      (node (ref "R327") (pin "2") (pinfunction "2_2") (pintype "passive"))
      (node (ref "R329") (pin "2") (pinfunction "2_2") (pintype "passive"))
      (node (ref "R331") (pin "2") (pinfunction "2_2") (pintype "passive"))
      (node (ref "R333") (pin "2") (pinfunction "2_2") (pintype "passive"))
      (node (ref "R336") (pin "2") (pinfunction "2_2") (pintype "passive"))
      (node (ref "R342") (pin "2") (pinfunction "2_2") (pintype "passive"))
      (node (ref "R357") (pin "1") (pinfunction "1_1") (pintype "passive"))
      (node (ref "R359") (pin "1") (pinfunction "1_1") (pintype "passive"))
      (node (ref "R360") (pin "1") (pinfunction "1_1") (pintype "passive"))
      (node (ref "R363") (pin "1") (pinfunction "1_1") (pintype "passive"))
      (node (ref "R366") (pin "2") (pinfunction "2_2") (pintype "passive"))
      (node (ref "R367") (pin "2") (pinfunction "2_2") (pintype "passive"))
      (node (ref "R368") (pin "2") (pinfunction "2_2") (pintype "passive"))
      (node (ref "R369") (pin "2") (pinfunction "2_2") (pintype "passive"))
      (node (ref "R370") (pin "2") (pinfunction "2_2") (pintype "passive"))
      (node (ref "R371") (pin "2") (pinfunction "2_2") (pintype "passive"))
      (node (ref "R373") (pin "2") (pinfunction "2_2") (pintype "passive"))
      (node (ref "R374") (pin "2") (pinfunction "2_2") (pintype "passive"))
      (node (ref "R375") (pin "1") (pinfunction "1_1") (pintype "passive"))
      (node (ref "R378") (pin "1") (pinfunction "1_1") (pintype "passive"))
      (node (ref "R67") (pin "2") (pinfunction "2_2") (pintype "passive"))
      (node (ref "TR1") (pin "1") (pinfunction "P1_1") (pintype "passive"))
      (node (ref "TR1") (pin "2") (pinfunction "P1_2") (pintype "passive"))
      (node (ref "TR1") (pin "5") (pinfunction "NC_5") (pintype "passive"))
    )
    (net (code "62") (name "Net-(C1-Pad1)") (class "Default")
      (node (ref "C1") (pin "1") (pinfunction "1_1") (pintype "passive"))
      (node (ref "R231") (pin "2") (pinfunction "2_2") (pintype "passive"))
    )
    (net (code "63") (name "Net-(C237-Pad1)") (class "Default")
      (node (ref "C237") (pin "1") (pinfunction "1_1") (pintype "passive"))
      (node (ref "R326") (pin "2") (pinfunction "2_2") (pintype "passive"))
    )
    (net (code "64") (name "Net-(C238-Pad1)") (class "Default")
      (node (ref "C238") (pin "1") (pinfunction "1_1") (pintype "passive"))
      (node (ref "R328") (pin "2") (pinfunction "2_2") (pintype "passive"))
    )
    (net (code "65") (name "Net-(C261-Pad1)") (class "Default")
      (node (ref "C261") (pin "1") (pinfunction "1_1") (pintype "passive"))
      (node (ref "R330") (pin "2") (pinfunction "2_2") (pintype "passive"))
    )
    (net (code "66") (name "Net-(C262-Pad1)") (class "Default")
      (node (ref "C262") (pin "1") (pinfunction "1_1") (pintype "passive"))
      (node (ref "R332") (pin "2") (pinfunction "2_2") (pintype "passive"))
    )
    (net (code "67") (name "Net-(C269-Pad1)") (class "Default")
      (node (ref "C269") (pin "1") (pinfunction "1_1") (pintype "passive"))
      (node (ref "J15") (pin "1") (pinfunction "1_1") (pintype "bidirectional"))
    )
    (net (code "68") (name "Net-(C269-Pad2)") (class "Default")
      (node (ref "C269") (pin "2") (pinfunction "2_2") (pintype "passive"))
      (node (ref "R294") (pin "2") (pinfunction "2_2") (pintype "passive"))
      (node (ref "TR1") (pin "3") (pinfunction "P1_3") (pintype "passive"))
    )
    (net (code "69") (name "Net-(C270-Pad2)") (class "Default")
      (node (ref "C270") (pin "2") (pinfunction "2_2") (pintype "passive"))
      (node (ref "C271") (pin "2") (pinfunction "2_2") (pintype "passive"))
    )
    (net (code "70") (name "Net-(C271-Pad1)") (class "Default")
      (node (ref "C271") (pin "1") (pinfunction "1_1") (pintype "passive"))
      (node (ref "C373") (pin "1") (pinfunction "1_1") (pintype "passive"))
      (node (ref "C680") (pin "1") (pinfunction "1_1") (pintype "passive"))
      (node (ref "R294") (pin "1") (pinfunction "1_1") (pintype "passive"))
      (node (ref "TR1") (pin "6") (pinfunction "S1_6") (pintype "passive"))
    )
    (net (code "71") (name "Net-(C272-Pad2)") (class "Default")
      (node (ref "C272") (pin "2") (pinfunction "2_2") (pintype "passive"))
      (node (ref "C273") (pin "2") (pinfunction "2_2") (pintype "passive"))
    )
    (net (code "72") (name "Net-(C273-Pad1)") (class "Default")
      (node (ref "C273") (pin "1") (pinfunction "1_1") (pintype "passive"))
      (node (ref "C374") (pin "1") (pinfunction "1_1") (pintype "passive"))
      (node (ref "C681") (pin "1") (pinfunction "1_1") (pintype "passive"))
      (node (ref "R295") (pin "2") (pinfunction "2_2") (pintype "passive"))
      (node (ref "TR1") (pin "4") (pinfunction "S1_4") (pintype "passive"))
    )
    (net (code "73") (name "Net-(C274-Pad1)") (class "Default")
      (node (ref "C274") (pin "1") (pinfunction "1_1") (pintype "passive"))
      (node (ref "R334") (pin "2") (pinfunction "2_2") (pintype "passive"))
    )
    (net (code "74") (name "Net-(C276-Pad1)") (class "Default")
      (node (ref "C276") (pin "1") (pinfunction "1_1") (pintype "passive"))
      (node (ref "R359") (pin "2") (pinfunction "2_2") (pintype "passive"))
      (node (ref "R376") (pin "1") (pinfunction "1_1") (pintype "passive"))
    )
    (net (code "75") (name "Net-(C344-Pad1)") (class "Default")
      (node (ref "C344") (pin "1") (pinfunction "1_1") (pintype "passive"))
      (node (ref "R377") (pin "1") (pinfunction "1_1") (pintype "passive"))
      (node (ref "R378") (pin "2") (pinfunction "2_2") (pintype "passive"))
      (node (ref "R379") (pin "2") (pinfunction "2_2") (pintype "passive"))
    )
    (net (code "76") (name "Net-(C358-Pad1)") (class "Default")
      (node (ref "C358") (pin "1") (pinfunction "1_1") (pintype "passive"))
      (node (ref "R532") (pin "2") (pinfunction "2_2") (pintype "passive"))
    )
    (net (code "77") (name "Net-(C359-Pad1)") (class "Default")
      (node (ref "C359") (pin "1") (pinfunction "1_1") (pintype "passive"))
      (node (ref "R534") (pin "2") (pinfunction "2_2") (pintype "passive"))
    )
    (net (code "78") (name "Net-(C361-Pad1)") (class "Default")
      (node (ref "C361") (pin "1") (pinfunction "1_1") (pintype "passive"))
      (node (ref "R533") (pin "2") (pinfunction "2_2") (pintype "passive"))
    )
    (net (code "79") (name "Net-(C362-Pad1)") (class "Default")
      (node (ref "C362") (pin "1") (pinfunction "1_1") (pintype "passive"))
      (node (ref "R531") (pin "2") (pinfunction "2_2") (pintype "passive"))
    )
    (net (code "80") (name "Net-(C375-Pad1)") (class "Default")
      (node (ref "C375") (pin "1") (pinfunction "1_1") (pintype "passive"))
      (node (ref "J31") (pin "1") (pinfunction "1_1") (pintype "bidirectional"))
    )
    (net (code "81") (name "Net-(C376-Pad1)") (class "Default")
      (node (ref "C376") (pin "1") (pinfunction "1_1") (pintype "passive"))
      (node (ref "J32") (pin "1") (pinfunction "1_1") (pintype "bidirectional"))
    )
    (net (code "82") (name "Net-(C377-Pad2)") (class "Default")
      (node (ref "C377") (pin "2") (pinfunction "2_2") (pintype "passive"))
      (node (ref "R361") (pin "2") (pinfunction "2_2") (pintype "passive"))
      (node (ref "R362") (pin "2") (pinfunction "2_2") (pintype "passive"))
      (node (ref "R381") (pin "2") (pinfunction "2_2") (pintype "passive"))
    )
    (net (code "83") (name "Net-(C407-Pad1)") (class "Default")
      (node (ref "C407") (pin "1") (pinfunction "1_1") (pintype "passive"))
      (node (ref "R341") (pin "2") (pinfunction "2_2") (pintype "passive"))
    )
    (net (code "84") (name "Net-(C448-Pad1)") (class "Default")
      (node (ref "C448") (pin "1") (pinfunction "1_1") (pintype "passive"))
      (node (ref "R343") (pin "2") (pinfunction "2_2") (pintype "passive"))
    )
    (net (code "85") (name "Net-(C531-Pad2)") (class "Default")
      (node (ref "C531") (pin "2") (pinfunction "2_2") (pintype "passive"))
      (node (ref "R313") (pin "2") (pinfunction "2_2") (pintype "passive"))
      (node (ref "R364") (pin "2") (pinfunction "2_2") (pintype "passive"))
      (node (ref "R365") (pin "2") (pinfunction "2_2") (pintype "passive"))
    )
    (net (code "86") (name "Net-(C680-Pad2)") (class "Default")
      (node (ref "C680") (pin "2") (pinfunction "2_2") (pintype "passive"))
      (node (ref "R552") (pin "2") (pinfunction "2_2") (pintype "passive"))
    )
    (net (code "87") (name "Net-(C681-Pad2)") (class "Default")
      (node (ref "C681") (pin "2") (pinfunction "2_2") (pintype "passive"))
      (node (ref "R553") (pin "2") (pinfunction "2_2") (pintype "passive"))
    )
    (net (code "88") (name "Net-(C682-Pad1)") (class "Default")
      (node (ref "C682") (pin "1") (pinfunction "1_1") (pintype "passive"))
      (node (ref "J19") (pin "1") (pinfunction "1_1") (pintype "bidirectional"))
    )
    (net (code "89") (name "Net-(C682-Pad2)") (class "Default")
      (node (ref "C682") (pin "2") (pinfunction "2_2") (pintype "passive"))
      (node (ref "R551") (pin "1") (pinfunction "1_1") (pintype "passive"))
      (node (ref "R552") (pin "1") (pinfunction "1_1") (pintype "passive"))
    )
    (net (code "90") (name "Net-(C683-Pad1)") (class "Default")
      (node (ref "C683") (pin "1") (pinfunction "1_1") (pintype "passive"))
      (node (ref "J20") (pin "1") (pinfunction "1_1") (pintype "bidirectional"))
    )
    (net (code "91") (name "Net-(C683-Pad2)") (class "Default")
      (node (ref "C683") (pin "2") (pinfunction "2_2") (pintype "passive"))
      (node (ref "R551") (pin "2") (pinfunction "2_2") (pintype "passive"))
      (node (ref "R553") (pin "1") (pinfunction "1_1") (pintype "passive"))
    )
    (net (code "92") (name "Net-(IC1-NR)") (class "Default")
      (node (ref "C360") (pin "2") (pinfunction "2_2") (pintype "passive"))
      (node (ref "IC1") (pin "5") (pinfunction "NR_5") (pintype "passive"))
    )
    (net (code "93") (name "Net-(IC43-CKIN2+)") (class "Default")
      (node (ref "C341") (pin "1") (pinfunction "1_1") (pintype "passive"))
      (node (ref "IC43") (pin "12") (pinfunction "CKIN2+_12") (pintype "input"))
    )
    (net (code "94") (name "Net-(IC43-CKIN2-)") (class "Default")
      (node (ref "C342") (pin "1") (pinfunction "1_1") (pintype "passive"))
      (node (ref "IC43") (pin "13") (pinfunction "CKIN2-_13") (pintype "input"))
    )
    (net (code "95") (name "Net-(IC43-CKOUT2+)") (class "Default")
      (node (ref "C266") (pin "1") (pinfunction "1_1") (pintype "passive"))
      (node (ref "IC43") (pin "35") (pinfunction "CKOUT2+_35") (pintype "output"))
      (node (ref "TP14") (pin "1") (pinfunction "1_1") (pintype "bidirectional"))
    )
    (net (code "96") (name "Net-(IC43-CKOUT2-)") (class "Default")
      (node (ref "C267") (pin "1") (pinfunction "1_1") (pintype "passive"))
      (node (ref "IC43") (pin "34") (pinfunction "CKOUT2-_34") (pintype "output"))
      (node (ref "TP15") (pin "1") (pinfunction "1_1") (pintype "bidirectional"))
    )
    (net (code "97") (name "Net-(IC43-CS_CA)") (class "Default")
      (node (ref "IC43") (pin "21") (pinfunction "CS_CA_21") (pintype "bidirectional"))
      (node (ref "R357") (pin "2") (pinfunction "2_2") (pintype "passive"))
    )
    (net (code "98") (name "Net-(IC44-Q0)") (class "Default")
      (node (ref "IC44") (pin "30") (pinfunction "Q0_30") (pintype "output"))
      (node (ref "R366") (pin "1") (pinfunction "1_1") (pintype "passive"))
      (node (ref "R531") (pin "1") (pinfunction "1_1") (pintype "passive"))
    )
    (net (code "99") (name "Net-(IC44-Q1)") (class "Default")
      (node (ref "IC44") (pin "28") (pinfunction "Q1_28") (pintype "output"))
      (node (ref "R369") (pin "1") (pinfunction "1_1") (pintype "passive"))
      (node (ref "R533") (pin "1") (pinfunction "1_1") (pintype "passive"))
    )
    (net (code "100") (name "Net-(IC44-Q2)") (class "Default")
      (node (ref "C364") (pin "1") (pinfunction "1_1") (pintype "passive"))
      (node (ref "IC44") (pin "24") (pinfunction "Q2_24") (pintype "output"))
      (node (ref "R367") (pin "1") (pinfunction "1_1") (pintype "passive"))
    )
    (net (code "101") (name "Net-(IC44-Q3)") (class "Default")
      (node (ref "IC44") (pin "22") (pinfunction "Q3_22") (pintype "output"))
      (node (ref "R230") (pin "1") (pinfunction "1_1") (pintype "passive"))
      (node (ref "R231") (pin "1") (pinfunction "1_1") (pintype "passive"))
    )
    (net (code "102") (name "Net-(IC44-Q4)") (class "Default")
      (node (ref "IC44") (pin "20") (pinfunction "Q4_20") (pintype "output"))
      (node (ref "R326") (pin "1") (pinfunction "1_1") (pintype "passive"))
      (node (ref "R67") (pin "1") (pinfunction "1_1") (pintype "passive"))
    )
    (net (code "103") (name "Net-(IC44-Q5)") (class "Default")
      (node (ref "IC44") (pin "18") (pinfunction "Q5_18") (pintype "output"))
      (node (ref "R329") (pin "1") (pinfunction "1_1") (pintype "passive"))
      (node (ref "R330") (pin "1") (pinfunction "1_1") (pintype "passive"))
    )
    (net (code "104") (name "Net-(IC44-Q6)") (class "Default")
      (node (ref "IC44") (pin "14") (pinfunction "Q6_14") (pintype "output"))
      (node (ref "R336") (pin "1") (pinfunction "1_1") (pintype "passive"))
      (node (ref "R341") (pin "1") (pinfunction "1_1") (pintype "passive"))
    )
    (net (code "105") (name "Net-(IC44-Q7)") (class "Default")
      (node (ref "C369") (pin "1") (pinfunction "1_1") (pintype "passive"))
      (node (ref "IC44") (pin "12") (pinfunction "Q7_12") (pintype "output"))
      (node (ref "R373") (pin "1") (pinfunction "1_1") (pintype "passive"))
    )
    (net (code "106") (name "Net-(IC44-VREF0)") (class "Default")
      (node (ref "IC44") (pin "3") (pinfunction "VREF0_3") (pintype "input"))
      (node (ref "R372") (pin "2") (pinfunction "2_2") (pintype "passive"))
    )
    (net (code "107") (name "Net-(IC44-VREF1)") (class "Default")
      (node (ref "IC44") (pin "8") (pinfunction "VREF1_8") (pintype "input"))
      (node (ref "R380") (pin "2") (pinfunction "2_2") (pintype "passive"))
    )
    (net (code "108") (name "Net-(IC44-VT0)") (class "Default")
      (node (ref "C372") (pin "2") (pinfunction "2_2") (pintype "passive"))
      (node (ref "IC44") (pin "4") (pinfunction "VT0_4") (pintype "passive"))
      (node (ref "R372") (pin "1") (pinfunction "1_1") (pintype "passive"))
    )
    (net (code "109") (name "Net-(IC44-VT1)") (class "Default")
      (node (ref "C363") (pin "2") (pinfunction "2_2") (pintype "passive"))
      (node (ref "IC44") (pin "7") (pinfunction "VT1_7") (pintype "passive"))
      (node (ref "R380") (pin "1") (pinfunction "1_1") (pintype "passive"))
    )
    (net (code "110") (name "Net-(IC44-~{Q0})") (class "Default")
      (node (ref "IC44") (pin "29") (pinfunction "~{Q0}_29") (pintype "output"))
      (node (ref "R368") (pin "1") (pinfunction "1_1") (pintype "passive"))
      (node (ref "R532") (pin "1") (pinfunction "1_1") (pintype "passive"))
    )
    (net (code "111") (name "Net-(IC44-~{Q1})") (class "Default")
      (node (ref "IC44") (pin "27") (pinfunction "~{Q1}_27") (pintype "output"))
      (node (ref "R371") (pin "1") (pinfunction "1_1") (pintype "passive"))
      (node (ref "R534") (pin "1") (pinfunction "1_1") (pintype "passive"))
    )
    (net (code "112") (name "Net-(IC44-~{Q2})") (class "Default")
      (node (ref "IC44") (pin "23") (pinfunction "~{Q2}_23") (pintype "output"))
      (node (ref "R370") (pin "1") (pinfunction "1_1") (pintype "passive"))
    )
    (net (code "113") (name "Net-(IC44-~{Q3})") (class "Default")
      (node (ref "IC44") (pin "21") (pinfunction "~{Q3}_21") (pintype "output"))
      (node (ref "R333") (pin "1") (pinfunction "1_1") (pintype "passive"))
      (node (ref "R334") (pin "1") (pinfunction "1_1") (pintype "passive"))
    )
    (net (code "114") (name "Net-(IC44-~{Q4})") (class "Default")
      (node (ref "IC44") (pin "19") (pinfunction "~{Q4}_19") (pintype "output"))
      (node (ref "R327") (pin "1") (pinfunction "1_1") (pintype "passive"))
      (node (ref "R328") (pin "1") (pinfunction "1_1") (pintype "passive"))
    )
    (net (code "115") (name "Net-(IC44-~{Q5})") (class "Default")
      (node (ref "IC44") (pin "17") (pinfunction "~{Q5}_17") (pintype "output"))
      (node (ref "R331") (pin "1") (pinfunction "1_1") (pintype "passive"))
      (node (ref "R332") (pin "1") (pinfunction "1_1") (pintype "passive"))
    )
    (net (code "116") (name "Net-(IC44-~{Q6})") (class "Default")
      (node (ref "IC44") (pin "13") (pinfunction "~{Q6}_13") (pintype "output"))
      (node (ref "R342") (pin "1") (pinfunction "1_1") (pintype "passive"))
      (node (ref "R343") (pin "1") (pinfunction "1_1") (pintype "passive"))
    )
    (net (code "117") (name "Net-(IC44-~{Q7})") (class "Default")
      (node (ref "C370") (pin "1") (pinfunction "1_1") (pintype "passive"))
      (node (ref "IC44") (pin "11") (pinfunction "~{Q7}_11") (pintype "output"))
      (node (ref "R374") (pin "1") (pinfunction "1_1") (pintype "passive"))
    )
    (net (code "118") (name "Net-(J33-Pad1)") (class "Default")
      (node (ref "J33") (pin "1") (pinfunction "1_1") (pintype "bidirectional"))
      (node (ref "R386") (pin "1") (pinfunction "1_1") (pintype "passive"))
    )
    (net (code "119") (name "Net-(OSC4-CLK+)") (class "Default")
      (node (ref "OSC4") (pin "4") (pinfunction "CLK+_4") (pintype "passive"))
      (node (ref "R376") (pin "2") (pinfunction "2_2") (pintype "passive"))
    )
    (net (code "120") (name "Net-(OSC4-CLK-)") (class "Default")
      (node (ref "C277") (pin "1") (pinfunction "1_1") (pintype "passive"))
      (node (ref "OSC4") (pin "5") (pinfunction "CLK-_5") (pintype "passive"))
      (node (ref "R360") (pin "2") (pinfunction "2_2") (pintype "passive"))
    )
    (net (code "121") (name "Net-(OSC4-NC)") (class "Default")
      (node (ref "OSC4") (pin "2") (pinfunction "NC_2") (pintype "passive"))
      (node (ref "R382") (pin "1") (pinfunction "1_1") (pintype "passive"))
    )
    (net (code "122") (name "Net-(OSC4-OE)") (class "Default")
      (node (ref "OSC4") (pin "1") (pinfunction "OE_1") (pintype "passive"))
      (node (ref "R384") (pin "1") (pinfunction "1_1") (pintype "passive"))
    )
    (net (code "123") (name "Net-(OSC4-VDD)") (class "Default")
      (node (ref "C350") (pin "2") (pinfunction "2_2") (pintype "passive"))
      (node (ref "C351") (pin "2") (pinfunction "2_2") (pintype "passive"))
      (node (ref "C657") (pin "2") (pinfunction "2_2") (pintype "passive"))
      (node (ref "L18") (pin "2") (pinfunction "2_2") (pintype "passive"))
      (node (ref "OSC4") (pin "6") (pinfunction "VDD_6") (pintype "passive"))
    )
    (net (code "124") (name "Net-(OSC5-CLK+)") (class "Default")
      (node (ref "OSC5") (pin "4") (pinfunction "CLK+_4") (pintype "passive"))
      (node (ref "R377") (pin "2") (pinfunction "2_2") (pintype "passive"))
    )
    (net (code "125") (name "Net-(OSC5-CLK-)") (class "Default")
      (node (ref "C346") (pin "1") (pinfunction "1_1") (pintype "passive"))
      (node (ref "OSC5") (pin "5") (pinfunction "CLK-_5") (pintype "passive"))
      (node (ref "R363") (pin "2") (pinfunction "2_2") (pintype "passive"))
    )
    (net (code "126") (name "Net-(OSC5-NC)") (class "Default")
      (node (ref "OSC5") (pin "2") (pinfunction "NC_2") (pintype "passive"))
      (node (ref "R383") (pin "1") (pinfunction "1_1") (pintype "passive"))
    )
    (net (code "127") (name "Net-(OSC5-OE)") (class "Default")
      (node (ref "OSC5") (pin "1") (pinfunction "OE_1") (pintype "passive"))
      (node (ref "R385") (pin "1") (pinfunction "1_1") (pintype "passive"))
    )
    (net (code "128") (name "Net-(OSC5-VDD)") (class "Default")
      (node (ref "C356") (pin "2") (pinfunction "2_2") (pintype "passive"))
      (node (ref "C357") (pin "2") (pinfunction "2_2") (pintype "passive"))
      (node (ref "C658") (pin "2") (pinfunction "2_2") (pintype "passive"))
      (node (ref "L19") (pin "2") (pinfunction "2_2") (pintype "passive"))
      (node (ref "OSC5") (pin "6") (pinfunction "VDD_6") (pintype "passive"))
    )
    (net (code "129") (name "P3V3") (class "Default")
      (node (ref "R313") (pin "1") (pinfunction "1_1") (pintype "passive"))
      (node (ref "R381") (pin "1") (pinfunction "1_1") (pintype "passive"))
    )
    (net (code "130") (name "P3V3_CLK") (class "Default")
      (node (ref "C654") (pin "2") (pinfunction "2_2") (pintype "passive"))
      (node (ref "C655") (pin "2") (pinfunction "2_2") (pintype "passive"))
      (node (ref "IC1") (pin "4") (pinfunction "OUT_4") (pintype "power_in"))
      (node (ref "L16") (pin "1") (pinfunction "1_1") (pintype "passive"))
      (node (ref "L18") (pin "1") (pinfunction "1_1") (pintype "passive"))
      (node (ref "L19") (pin "1") (pinfunction "1_1") (pintype "passive"))
      (node (ref "L20") (pin "1") (pinfunction "1_1") (pintype "passive"))
    )
    (net (code "131") (name "P5V0") (class "Default")
      (node (ref "L17") (pin "1") (pinfunction "1_1") (pintype "passive"))
    )
    (net (code "132") (name "unconnected-(C237-Pad2)") (class "Default")
      (node (ref "C237") (pin "2") (pinfunction "2_2") (pintype "passive"))
    )
    (net (code "133") (name "unconnected-(C238-Pad2)") (class "Default")
      (node (ref "C238") (pin "2") (pinfunction "2_2") (pintype "passive"))
    )
    (net (code "134") (name "unconnected-(C261-Pad2)") (class "Default")
      (node (ref "C261") (pin "2") (pinfunction "2_2") (pintype "passive"))
    )
    (net (code "135") (name "unconnected-(C262-Pad2)") (class "Default")
      (node (ref "C262") (pin "2") (pinfunction "2_2") (pintype "passive"))
    )
    (net (code "136") (name "unconnected-(IC43-C2B-Pad4)") (class "Default")
      (node (ref "IC43") (pin "4") (pinfunction "C2B_4") (pintype "output+no_connect"))
    )
    (net (code "137") (name "unconnected-(IC43-CKOUT1+-Pad28)") (class "Default")
      (node (ref "IC43") (pin "28") (pinfunction "CKOUT1+_28") (pintype "output+no_connect"))
    )
    (net (code "138") (name "unconnected-(IC43-CKOUT1--Pad29)") (class "Default")
      (node (ref "IC43") (pin "29") (pinfunction "CKOUT1-_29") (pintype "output+no_connect"))
    )
    (net (code "139") (name "unconnected-(IC43-LOL-Pad18)") (class "Default")
      (node (ref "IC43") (pin "18") (pinfunction "LOL_18") (pintype "output+no_connect"))
    )
    (net (code "140") (name "unconnected-(IC43-NC-Pad2)") (class "Default")
      (node (ref "IC43") (pin "2") (pinfunction "NC_2") (pintype "passive+no_connect"))
    )
    (net (code "141") (name "unconnected-(IC43-NC-Pad9)") (class "Default")
      (node (ref "IC43") (pin "9") (pinfunction "NC_9") (pintype "passive+no_connect"))
    )
    (net (code "142") (name "unconnected-(IC43-NC-Pad14)") (class "Default")
      (node (ref "IC43") (pin "14") (pinfunction "NC_14") (pintype "passive+no_connect"))
    )
    (net (code "143") (name "unconnected-(IC43-NC-Pad30)") (class "Default")
      (node (ref "IC43") (pin "30") (pinfunction "NC_30") (pintype "passive+no_connect"))
    )
    (net (code "144") (name "unconnected-(IC43-NC-Pad33)") (class "Default")
      (node (ref "IC43") (pin "33") (pinfunction "NC_33") (pintype "passive+no_connect"))
    )
    (net (code "145") (name "unconnected-(IC43-RATE0-Pad11)") (class "Default")
      (node (ref "IC43") (pin "11") (pinfunction "RATE0_11") (pintype "input+no_connect"))
    )
    (net (code "146") (name "unconnected-(IC43-RATE1-Pad15)") (class "Default")
      (node (ref "IC43") (pin "15") (pinfunction "RATE1_15") (pintype "input+no_connect"))
    )
    (net (code "147") (name "unconnected-(IC43-SDI-Pad27)") (class "Default")
      (node (ref "IC43") (pin "27") (pinfunction "SDI_27") (pintype "input+no_connect"))
    )
    (net (code "148") (name "unconnected-(IC44-NC-Pad9)") (class "Default")
      (node (ref "IC44") (pin "9") (pinfunction "NC_9") (pintype "passive+no_connect"))
    )
    (net (code "149") (name "unconnected-(R296-Pad2)") (class "Default")
      (node (ref "R296") (pin "2") (pinfunction "2_2") (pintype "passive"))
    )
    (net (code "150") (name "unconnected-(R297-Pad2)") (class "Default")
      (node (ref "R297") (pin "2") (pinfunction "2_2") (pintype "passive"))
    )
  )
)
